# CANTensegrityBoard.net
KiCad netlist of a schematic drawn in EAGLE
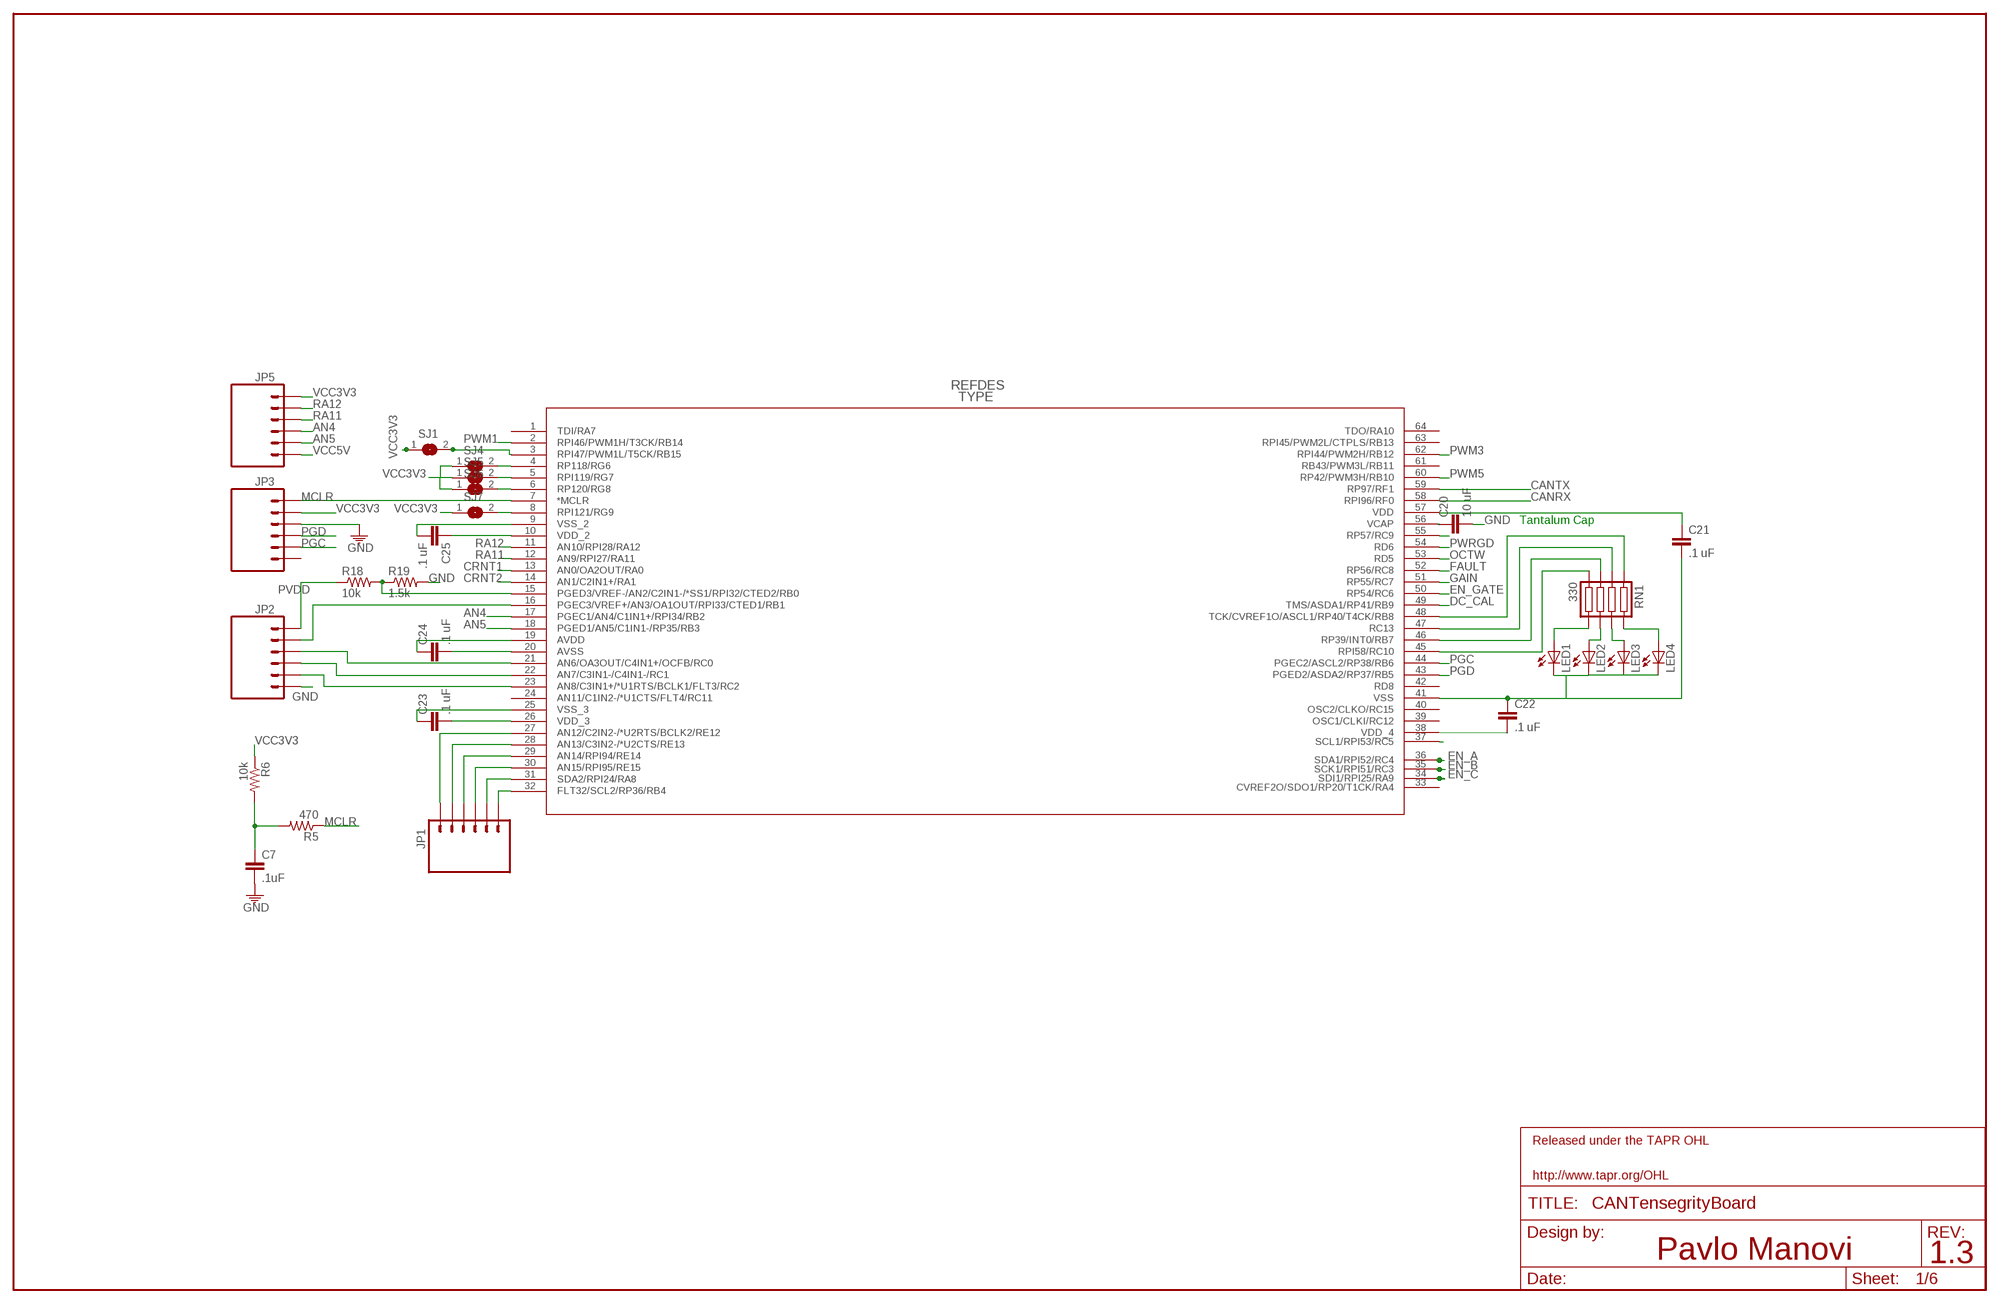
[diagram p0: schematic, sheet 1]
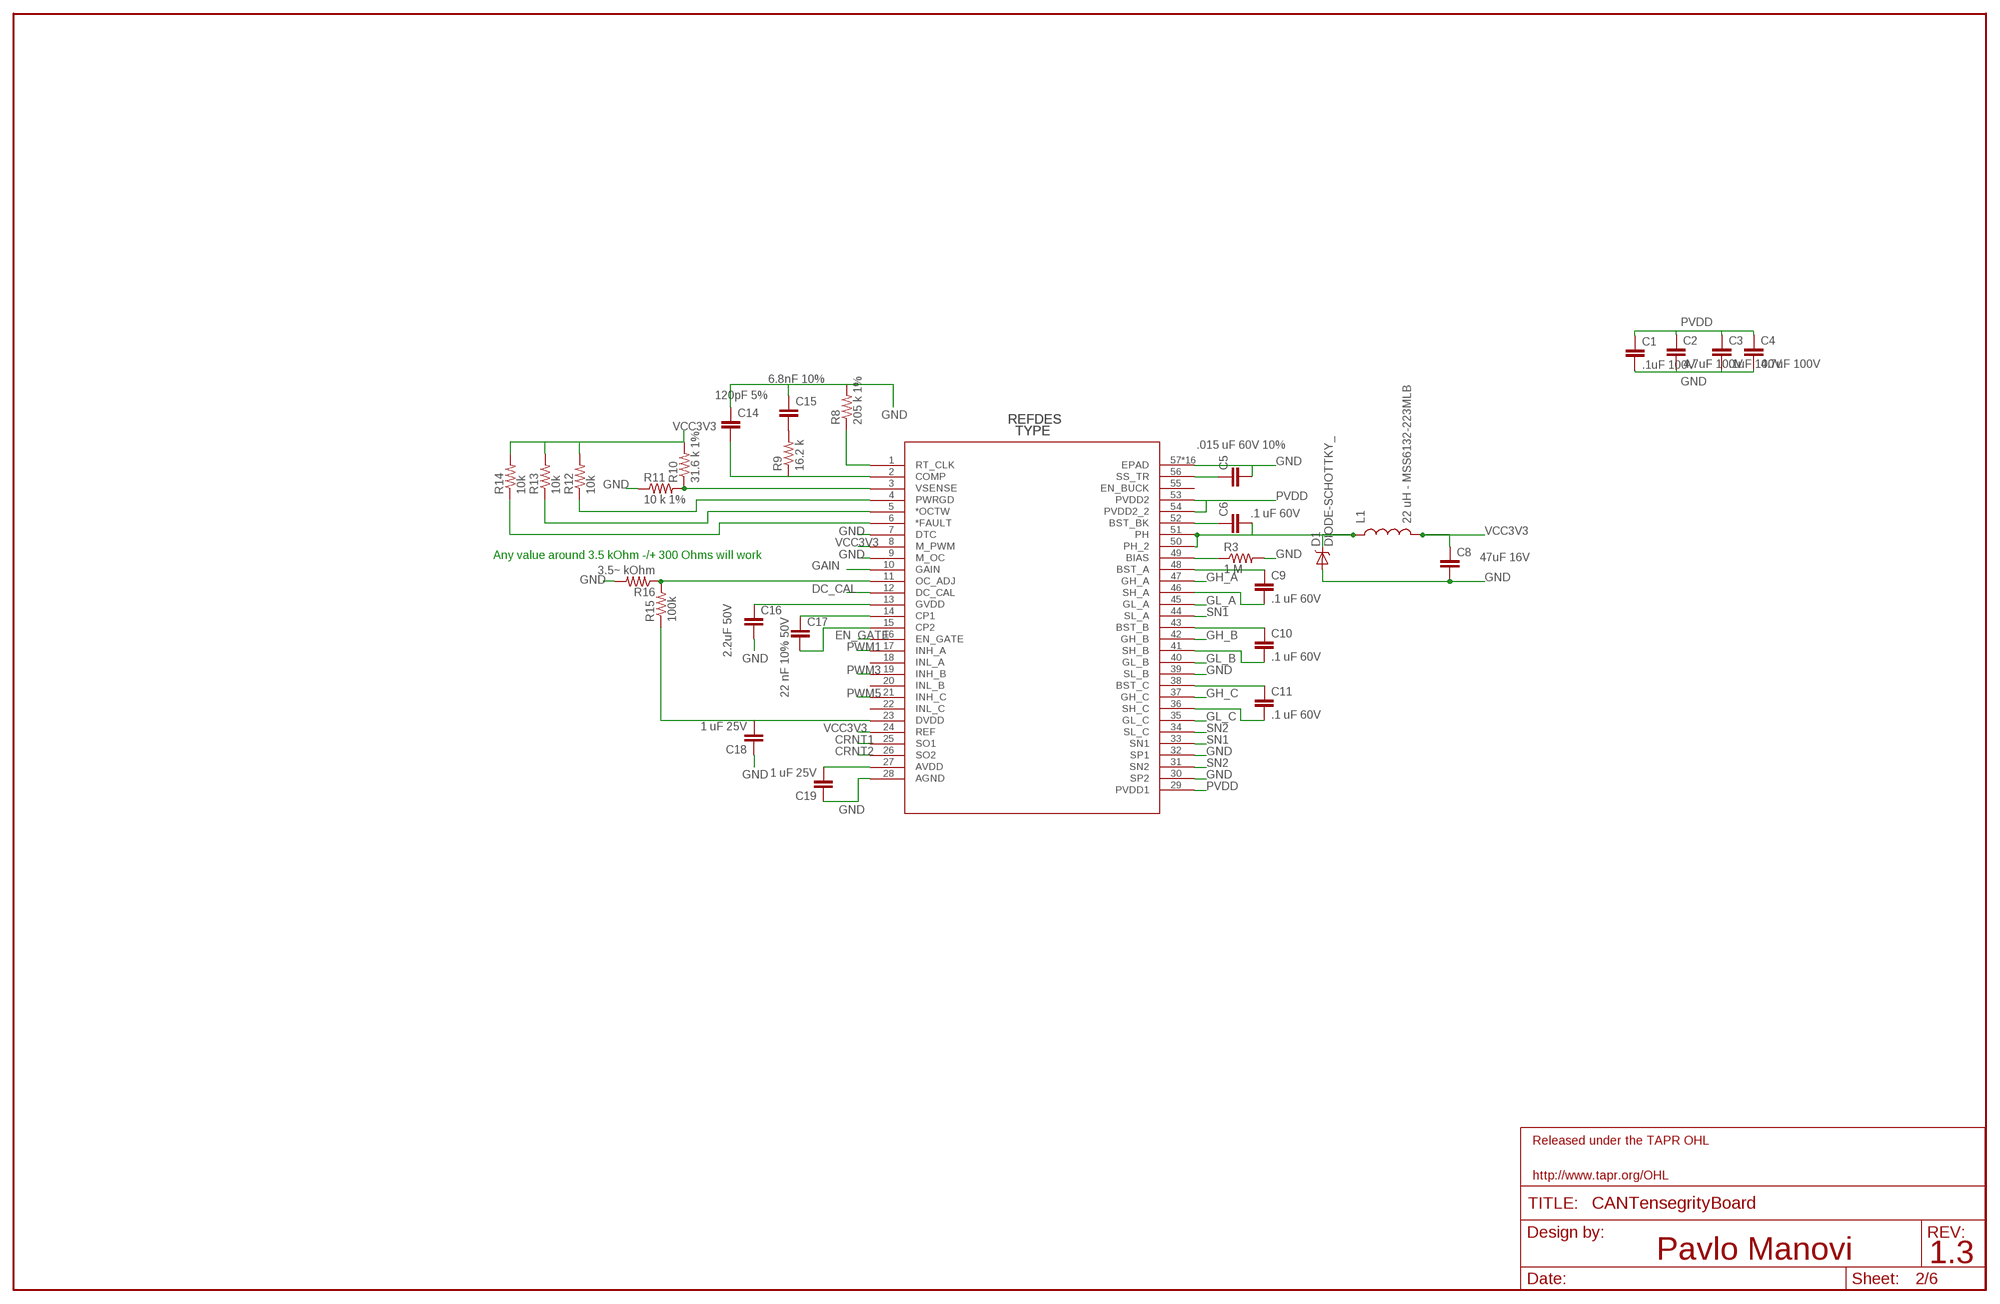
[diagram p1: schematic, sheet 2]
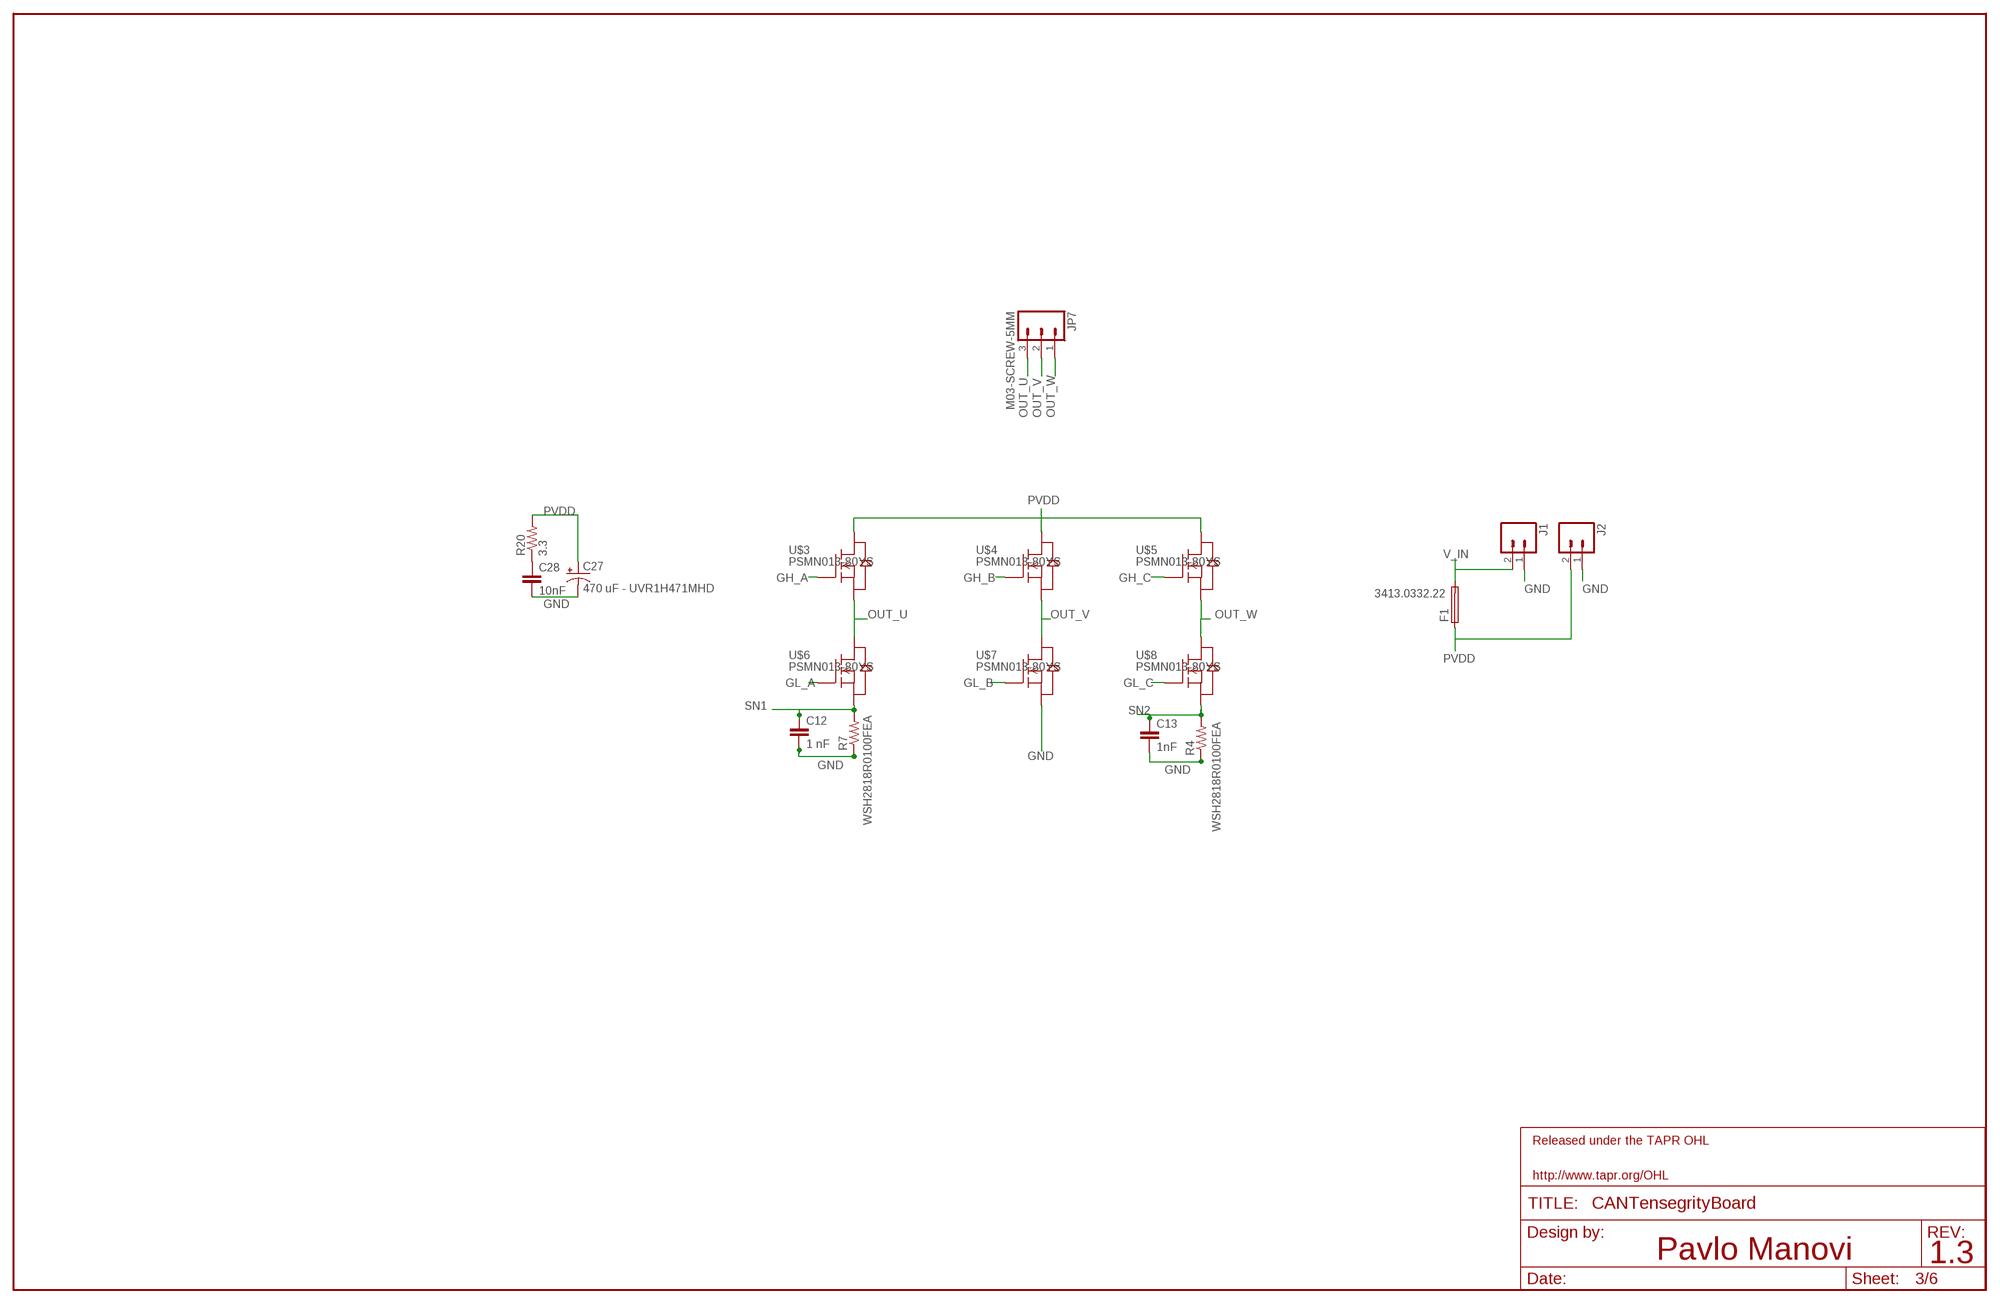
[diagram p2: schematic, sheet 3]
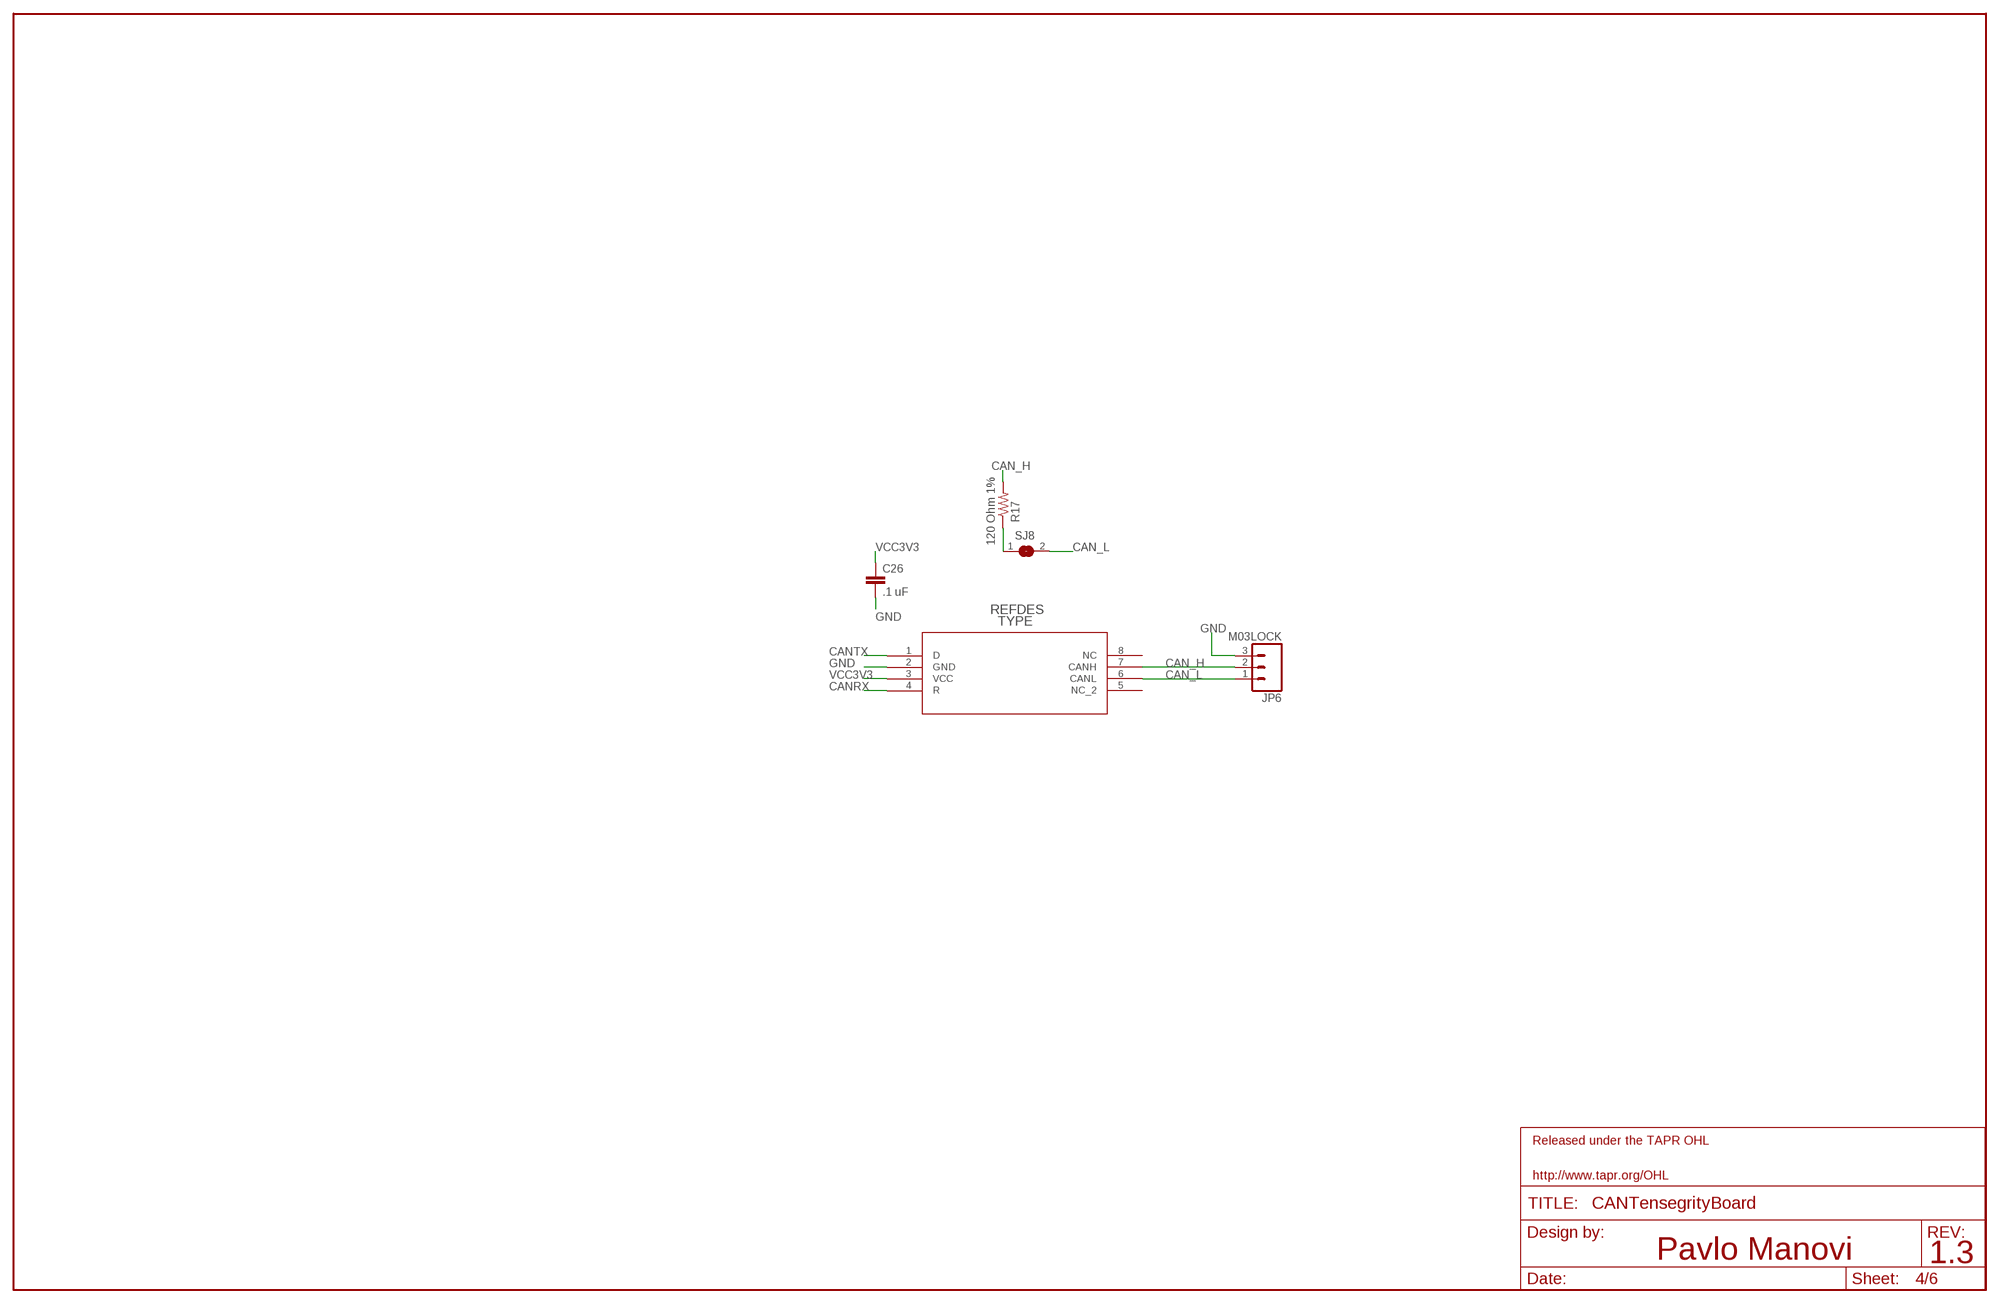
[diagram p3: schematic, sheet 4]
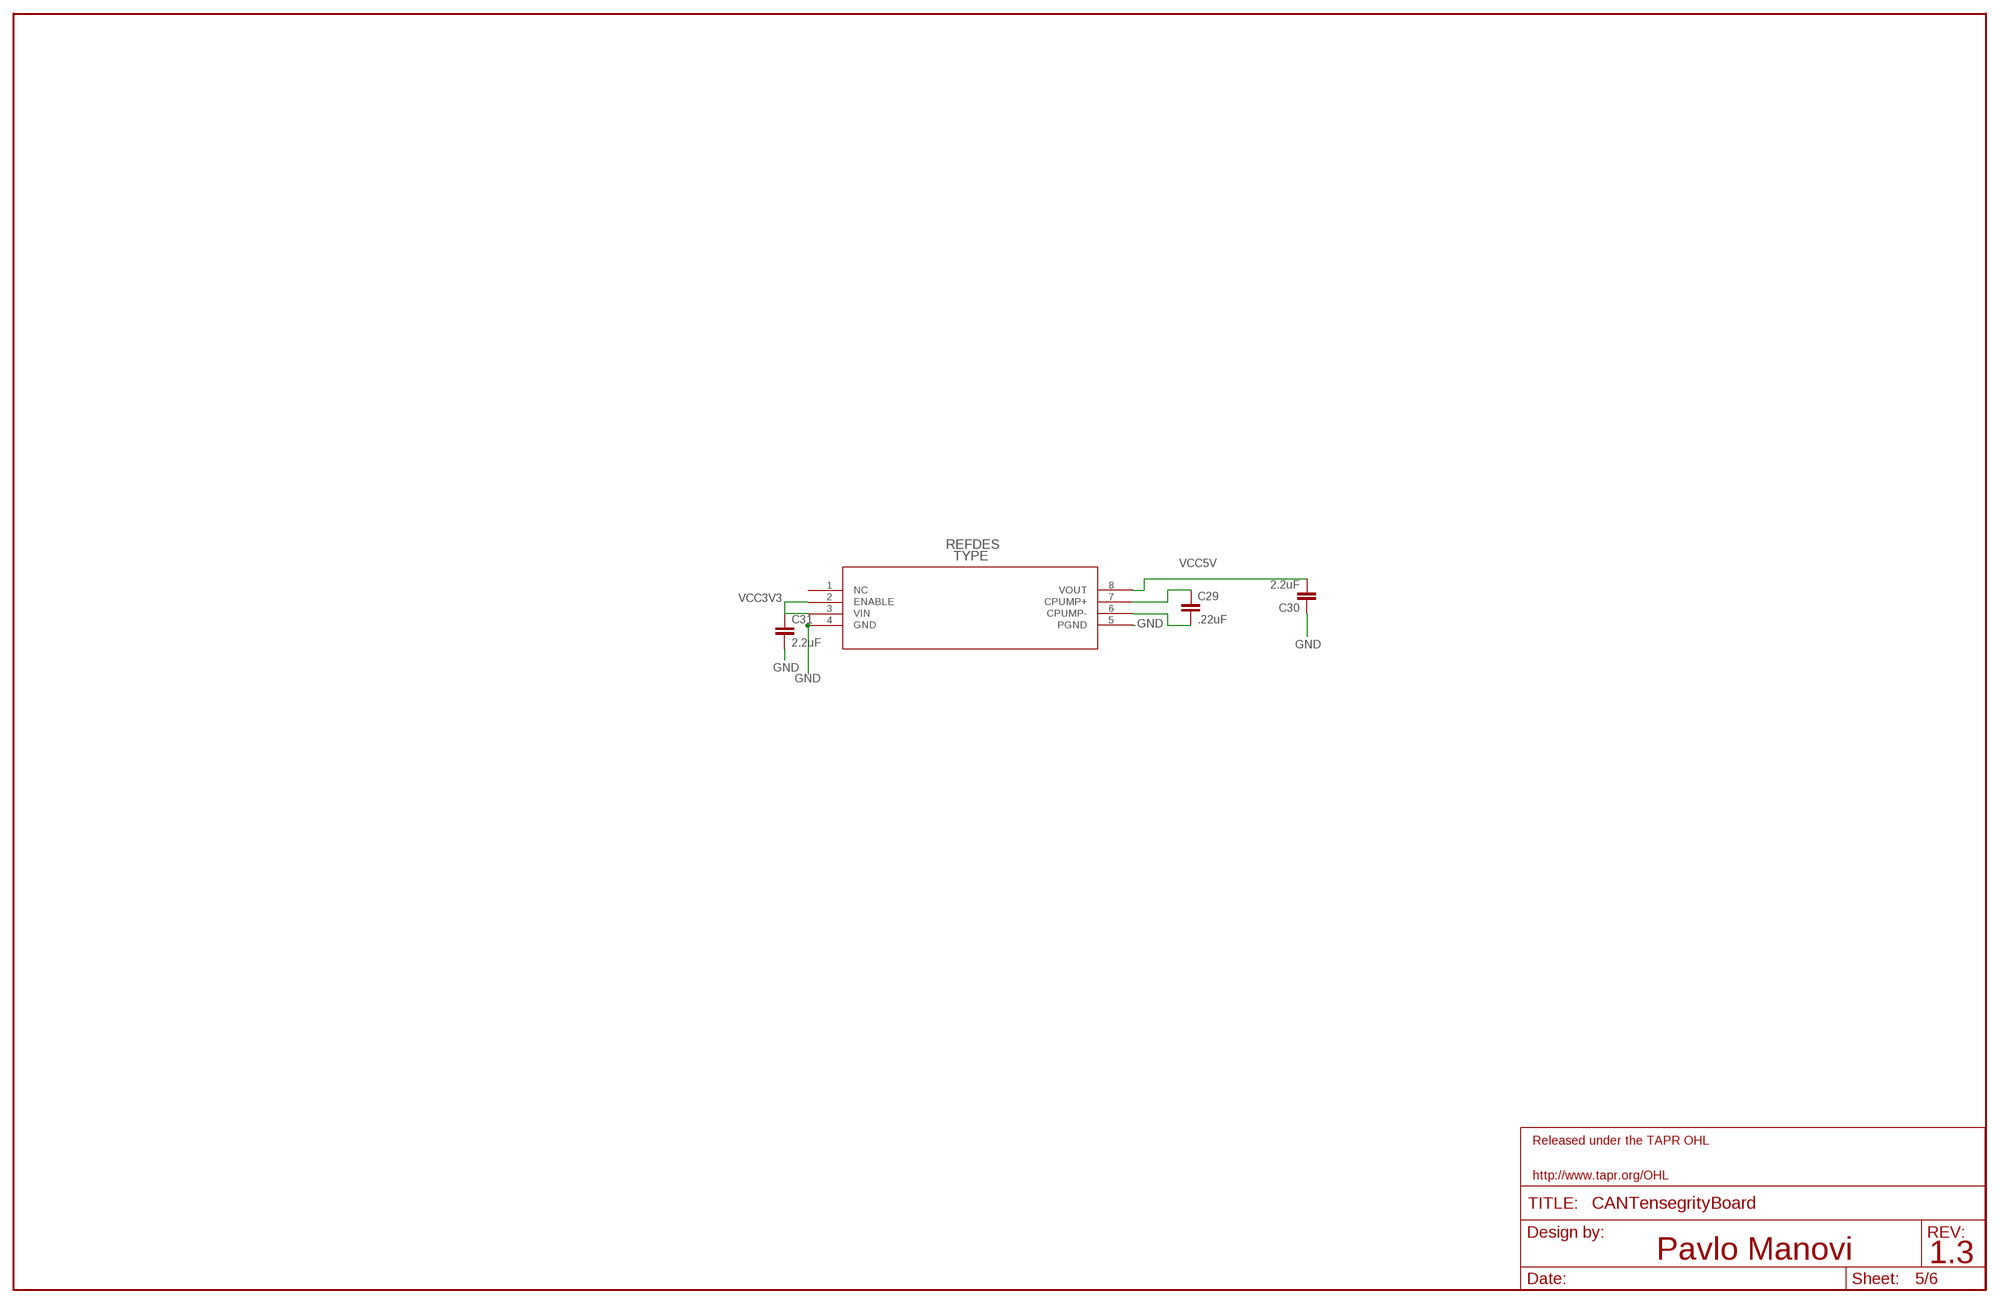
[diagram p4: schematic, sheet 5]
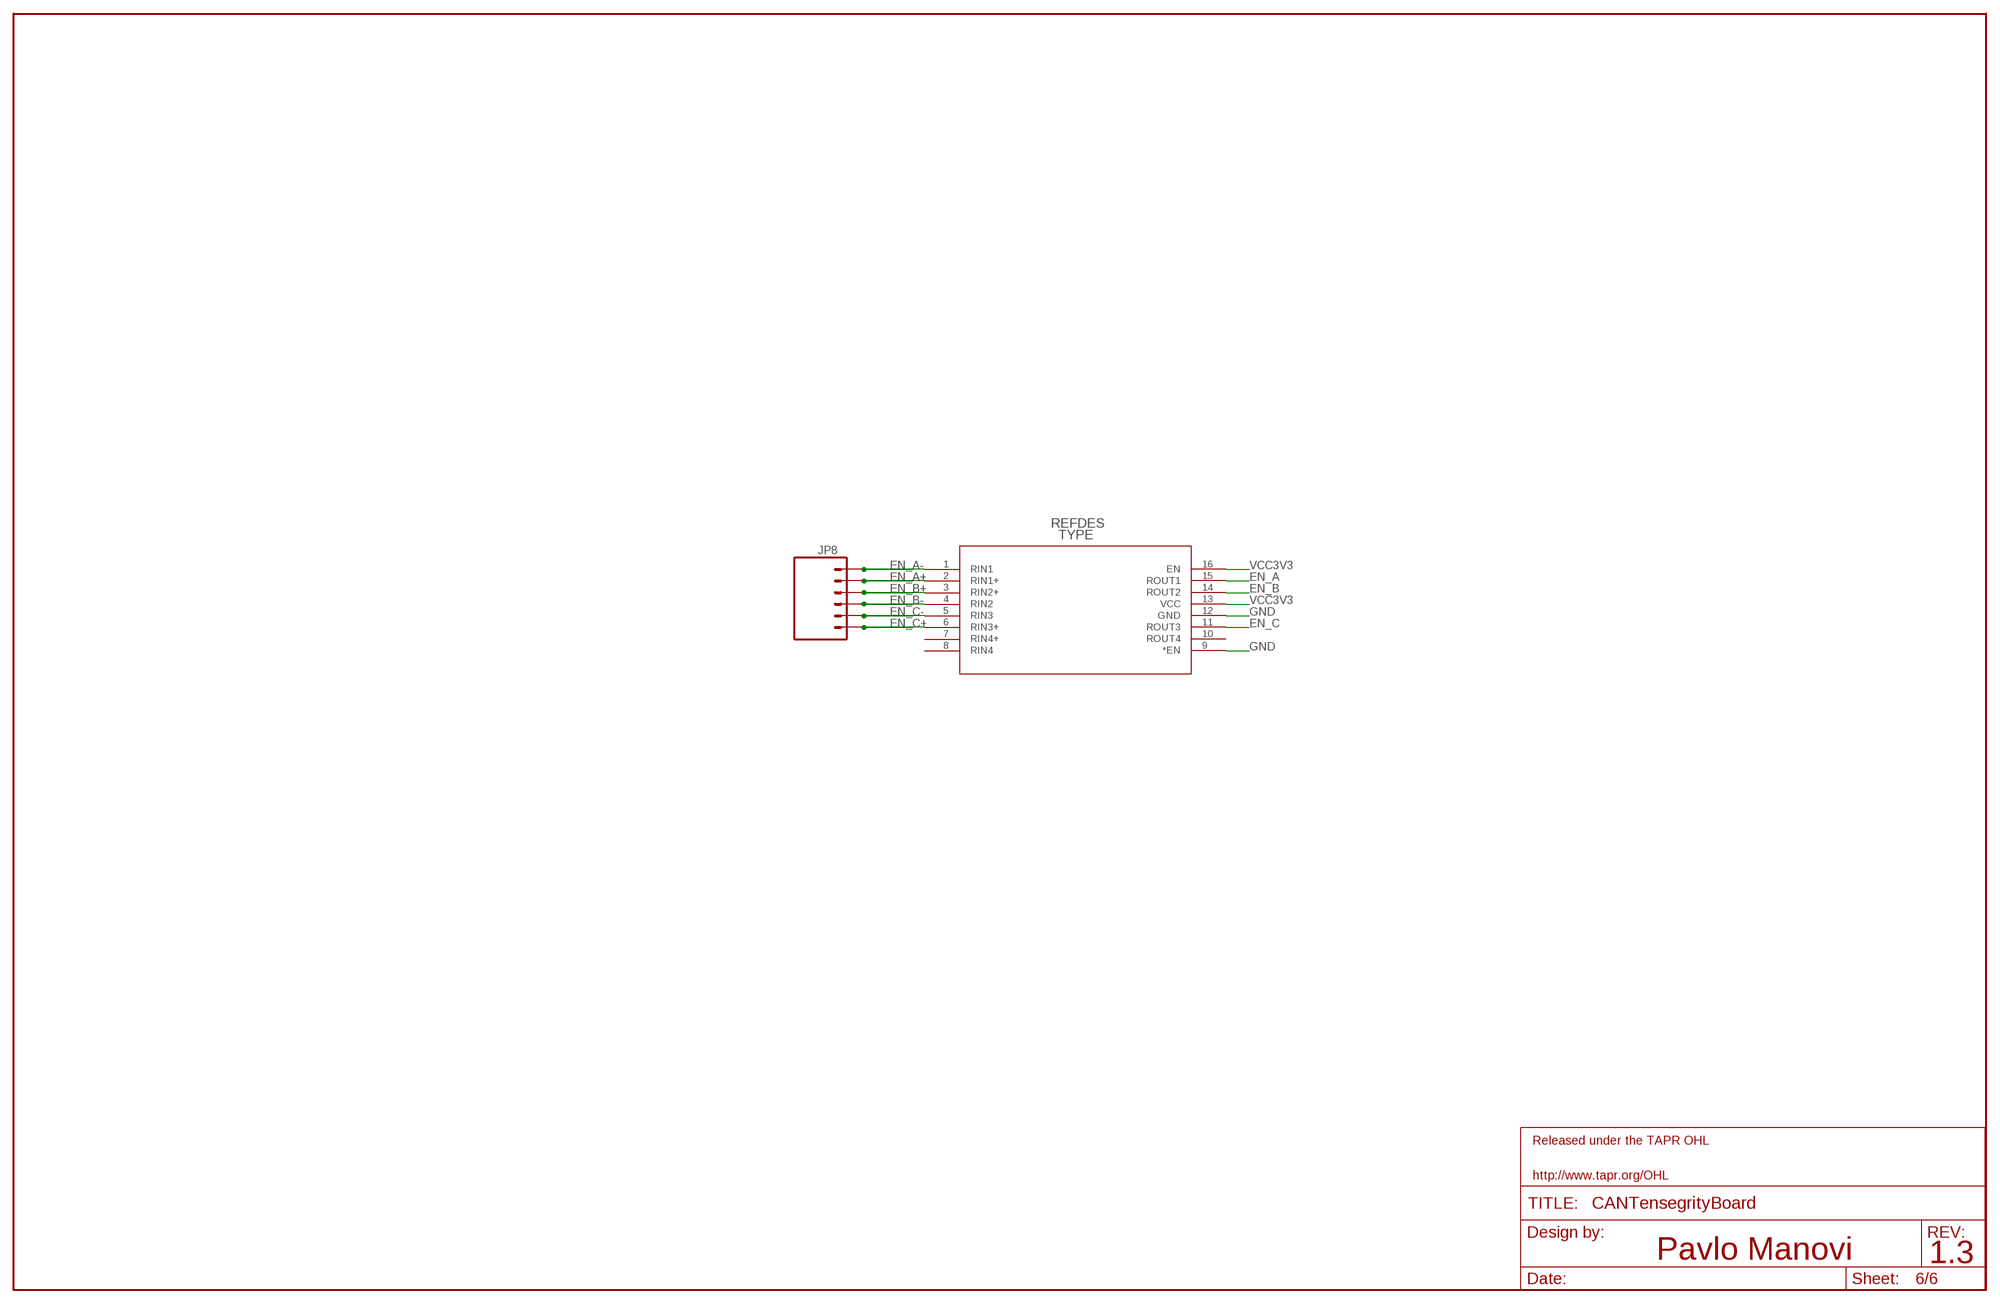
[diagram p5: schematic, sheet 6]

(export (version "E")
  (design (tool "Eeschema 10.0.6"))
  (components
    (comp (ref "C7")
      (value ".1uF")
      (footprint "eagle-import:0805")
      (libsource (lib "eagle-import") (part "CAP0805"))
    )
    (comp (ref "C20")
      (value "10 uF")
      (footprint "eagle-import:1206")
      (libsource (lib "eagle-import") (part "CAP1206"))
    )
    (comp (ref "C21")
      (value ".1 uF")
      (footprint "eagle-import:0805")
      (libsource (lib "eagle-import") (part "CAP0805"))
    )
    (comp (ref "C22")
      (value ".1 uF")
      (footprint "eagle-import:0805")
      (libsource (lib "eagle-import") (part "CAP0805"))
    )
    (comp (ref "C23")
      (value ".1 uF")
      (footprint "eagle-import:0805")
      (libsource (lib "eagle-import") (part "CAP0805"))
    )
    (comp (ref "C24")
      (value ".1 uF")
      (footprint "eagle-import:0805")
      (libsource (lib "eagle-import") (part "CAP0805"))
    )
    (comp (ref "C25")
      (value ".1 uF")
      (footprint "eagle-import:0805")
      (libsource (lib "eagle-import") (part "CAP0805"))
    )
    (comp (ref "JP1")
      (value "M06SIP")
      (footprint "eagle-import:1X06")
      (libsource (lib "eagle-import") (part "M06SIP"))
    )
    (comp (ref "JP2")
      (value "M06SIP")
      (footprint "eagle-import:1X06")
      (libsource (lib "eagle-import") (part "M06SIP"))
    )
    (comp (ref "JP3")
      (value "M06LOCK")
      (footprint "eagle-import:1X06_LOCK")
      (libsource (lib "eagle-import") (part "CMPE118lib_M06LOCK"))
    )
    (comp (ref "JP5")
      (value "M06LOCK")
      (footprint "eagle-import:1X06_LOCK")
      (libsource (lib "eagle-import") (part "CMPE118lib_M06LOCK"))
    )
    (comp (ref "LED1")
      (value "LED0805")
      (footprint "eagle-import:LED-0805")
      (libsource (lib "eagle-import") (part "LED0805"))
    )
    (comp (ref "LED2")
      (value "LED0805")
      (footprint "eagle-import:LED-0805")
      (libsource (lib "eagle-import") (part "LED0805"))
    )
    (comp (ref "LED3")
      (value "LED0805")
      (footprint "eagle-import:LED-0805")
      (libsource (lib "eagle-import") (part "LED0805"))
    )
    (comp (ref "LED4")
      (value "LED0805")
      (footprint "eagle-import:LED-0805")
      (libsource (lib "eagle-import") (part "LED0805"))
    )
    (comp (ref "R5")
      (value "470")
      (footprint "eagle-import:0805")
      (libsource (lib "eagle-import") (part "CMPE118lib_RESISTOR0805-RES"))
    )
    (comp (ref "R6")
      (value "10k")
      (footprint "eagle-import:0805")
      (libsource (lib "eagle-import") (part "CMPE118lib_RESISTOR0805-RES"))
    )
    (comp (ref "R18")
      (value "10k")
      (footprint "eagle-import:0805")
      (libsource (lib "eagle-import") (part "RESISTOR0805-RES"))
    )
    (comp (ref "R19")
      (value "1.5k")
      (footprint "eagle-import:0805")
      (libsource (lib "eagle-import") (part "RESISTOR0805-RES"))
    )
    (comp (ref "RN1")
      (value "330")
      (footprint "eagle-import:EXB-38V271JV")
      (libsource (lib "eagle-import") (part "RESISTOR_ARRAY-4"))
    )
    (comp (ref "SJ1") (value "SJ") (footprint "eagle-import:SJ") (libsource (lib "eagle-import") (part "SJ")))
    (comp (ref "SJ4") (value "SJ") (footprint "eagle-import:SJ") (libsource (lib "eagle-import") (part "SJ")))
    (comp (ref "SJ5") (value "SJ") (footprint "eagle-import:SJ") (libsource (lib "eagle-import") (part "SJ")))
    (comp (ref "SJ6") (value "SJ") (footprint "eagle-import:SJ") (libsource (lib "eagle-import") (part "SJ")))
    (comp (ref "SJ7") (value "SJ") (footprint "eagle-import:SJ") (libsource (lib "eagle-import") (part "SJ")))
    (comp (ref "U$1")
      (value "DSPIC33EP128MC502-I/SS")
      (footprint "eagle-import:QFP64-10X10MC")
      (libsource (lib "eagle-import") (part "DSPIC33EP256MC50"))
    )
    (comp (ref "C29")
      (value ".22uF")
      (footprint "eagle-import:0805")
      (libsource (lib "eagle-import") (part "CAP0805"))
    )
    (comp (ref "C30")
      (value "2.2uF")
      (footprint "eagle-import:0805")
      (libsource (lib "eagle-import") (part "CAP0805"))
    )
    (comp (ref "C31")
      (value "2.2uF")
      (footprint "eagle-import:0805")
      (libsource (lib "eagle-import") (part "CAP0805"))
    )
    (comp (ref "U1")
      (value "REG711-5_DGK_8")
      (footprint "eagle-import:DGK8")
      (libsource (lib "eagle-import") (part "REG711-5_DGK_8"))
    )
    (comp (ref "JP8")
      (value "M06SIP_LOCK")
      (footprint "eagle-import:1X06-SIP_LOCK")
      (libsource (lib "eagle-import") (part "M06SIP_LOCK"))
    )
    (comp (ref "U3")
      (value "SN65LVDT348_PW_1")
      (footprint "eagle-import:PW16")
      (libsource (lib "eagle-import") (part "SN65LVDT348_PW_1"))
    )
    (comp (ref "C12")
      (value "1 nF")
      (footprint "eagle-import:0805")
      (libsource (lib "eagle-import") (part "CAP0805"))
    )
    (comp (ref "C13")
      (value "1nF")
      (footprint "eagle-import:0805")
      (libsource (lib "eagle-import") (part "CAP0805"))
    )
    (comp (ref "C27")
      (value "470 uF - UVR1H471MHD")
      (footprint "eagle-import:CPOL-RADIAL-1000UF-25V")
      (libsource (lib "eagle-import") (part "CAP_POLPTH4"))
    )
    (comp (ref "C28")
      (value "10nF")
      (footprint "eagle-import:0805")
      (libsource (lib "eagle-import") (part "CAP0805"))
    )
    (comp (ref "F1")
      (value "3413.0332.22")
      (footprint "eagle-import:LED-1206")
      (libsource (lib "eagle-import") (part "TE5"))
    )
    (comp (ref "J1")
      (value "M02PTH4")
      (footprint "eagle-import:1X02_XTRA_BIG")
      (libsource (lib "eagle-import") (part "M02PTH4"))
    )
    (comp (ref "J2")
      (value "M02PTH4")
      (footprint "eagle-import:1X02_XTRA_BIG")
      (libsource (lib "eagle-import") (part "M02PTH4"))
    )
    (comp (ref "JP7")
      (value "M03-SCREW-5MM")
      (footprint "eagle-import:SCREWTERMINAL-5MM-3")
      (libsource (lib "eagle-import") (part "pavlo_M03-SCREW-5MM"))
    )
    (comp (ref "R4")
      (value "WSH2818R0100FEA")
      (footprint "eagle-import:SMT-REF")
      (libsource (lib "eagle-import") (part "RESISTOR"))
    )
    (comp (ref "R7")
      (value "WSH2818R0100FEA")
      (footprint "eagle-import:SMT-REF")
      (libsource (lib "eagle-import") (part "RESISTOR"))
    )
    (comp (ref "R20")
      (value "3.3")
      (footprint "eagle-import:0805")
      (libsource (lib "eagle-import") (part "RESISTOR0805-RES"))
    )
    (comp (ref "U$3")
      (value "PSMN013-80YS")
      (footprint "eagle-import:TO127P600X120-5N")
      (libsource (lib "eagle-import") (part "PSMN013-80YS"))
    )
    (comp (ref "U$4")
      (value "PSMN013-80YS")
      (footprint "eagle-import:TO127P600X120-5N")
      (libsource (lib "eagle-import") (part "PSMN013-80YS"))
    )
    (comp (ref "U$5")
      (value "PSMN013-80YS")
      (footprint "eagle-import:TO127P600X120-5N")
      (libsource (lib "eagle-import") (part "PSMN013-80YS"))
    )
    (comp (ref "U$6")
      (value "PSMN013-80YS")
      (footprint "eagle-import:TO127P600X120-5N")
      (libsource (lib "eagle-import") (part "PSMN013-80YS"))
    )
    (comp (ref "U$7")
      (value "PSMN013-80YS")
      (footprint "eagle-import:TO127P600X120-5N")
      (libsource (lib "eagle-import") (part "PSMN013-80YS"))
    )
    (comp (ref "U$8")
      (value "PSMN013-80YS")
      (footprint "eagle-import:TO127P600X120-5N")
      (libsource (lib "eagle-import") (part "PSMN013-80YS"))
    )
    (comp (ref "C1")
      (value ".1uF 100V")
      (footprint "eagle-import:0805")
      (libsource (lib "eagle-import") (part "CAP0805"))
    )
    (comp (ref "C2")
      (value "4.7uF 100V")
      (footprint "eagle-import:1206")
      (libsource (lib "eagle-import") (part "CAP1206"))
    )
    (comp (ref "C3")
      (value ".1uF 100V")
      (footprint "eagle-import:0805")
      (libsource (lib "eagle-import") (part "CAP0805"))
    )
    (comp (ref "C4")
      (value "4.7uF 100V")
      (footprint "eagle-import:1206")
      (libsource (lib "eagle-import") (part "CAP1206"))
    )
    (comp (ref "C5")
      (value ".015 uF 60V 10%")
      (footprint "eagle-import:0805")
      (libsource (lib "eagle-import") (part "CAP0805"))
    )
    (comp (ref "C6")
      (value ".1 uF 60V")
      (footprint "eagle-import:0805")
      (libsource (lib "eagle-import") (part "CAP0805"))
    )
    (comp (ref "C8")
      (value "47uF 16V")
      (footprint "eagle-import:1206")
      (libsource (lib "eagle-import") (part "CAP1206"))
    )
    (comp (ref "C9")
      (value ".1 uF 60V")
      (footprint "eagle-import:0805")
      (libsource (lib "eagle-import") (part "CAP0805"))
    )
    (comp (ref "C10")
      (value ".1 uF 60V")
      (footprint "eagle-import:0805")
      (libsource (lib "eagle-import") (part "CAP0805"))
    )
    (comp (ref "C11")
      (value ".1 uF 60V")
      (footprint "eagle-import:0805")
      (libsource (lib "eagle-import") (part "CAP0805"))
    )
    (comp (ref "C14")
      (value "120pF 5%")
      (footprint "eagle-import:0805")
      (libsource (lib "eagle-import") (part "CAP0805"))
    )
    (comp (ref "C15")
      (value "6.8nF 10%")
      (footprint "eagle-import:0805")
      (libsource (lib "eagle-import") (part "CAP0805"))
    )
    (comp (ref "C16")
      (value "2.2uF 50V")
      (footprint "eagle-import:1206")
      (libsource (lib "eagle-import") (part "CAP1206"))
    )
    (comp (ref "C17")
      (value "22 nF 10% 50V")
      (footprint "eagle-import:0805")
      (libsource (lib "eagle-import") (part "CAP0805"))
    )
    (comp (ref "C18")
      (value "1 uF 25V")
      (footprint "eagle-import:0805")
      (libsource (lib "eagle-import") (part "CAP0805"))
    )
    (comp (ref "C19")
      (value "1 uF 25V")
      (footprint "eagle-import:0805")
      (libsource (lib "eagle-import") (part "CAP0805"))
    )
    (comp (ref "D1")
      (value "DIODE-SCHOTTKY_")
      (footprint "eagle-import:SMA-DIODE")
      (libsource (lib "eagle-import") (part "DIODE-SCHOTTKY_"))
    )
    (comp (ref "L1")
      (value "22 uH - MSS6132-223MLB")
      (footprint "eagle-import:MSS6132")
      (libsource (lib "eagle-import") (part "INDUCTOR"))
    )
    (comp (ref "R3")
      (value "1 M")
      (footprint "eagle-import:0805")
      (libsource (lib "eagle-import") (part "RESISTOR0805-RES"))
    )
    (comp (ref "R8")
      (value "205 k 1%")
      (footprint "eagle-import:0805")
      (libsource (lib "eagle-import") (part "RESISTOR0805-RES"))
    )
    (comp (ref "R9")
      (value "16.2 k")
      (footprint "eagle-import:0805")
      (libsource (lib "eagle-import") (part "RESISTOR0805-RES"))
    )
    (comp (ref "R10")
      (value "31.6 k 1%")
      (footprint "eagle-import:0805")
      (libsource (lib "eagle-import") (part "RESISTOR0805-RES"))
    )
    (comp (ref "R11")
      (value "10 k 1%")
      (footprint "eagle-import:0805")
      (libsource (lib "eagle-import") (part "RESISTOR0805-RES"))
    )
    (comp (ref "R12")
      (value "10k")
      (footprint "eagle-import:0805")
      (libsource (lib "eagle-import") (part "RESISTOR0805-RES"))
    )
    (comp (ref "R13")
      (value "10k")
      (footprint "eagle-import:0805")
      (libsource (lib "eagle-import") (part "RESISTOR0805-RES"))
    )
    (comp (ref "R14")
      (value "10k")
      (footprint "eagle-import:0805")
      (libsource (lib "eagle-import") (part "RESISTOR0805-RES"))
    )
    (comp (ref "R15")
      (value "100k")
      (footprint "eagle-import:0805")
      (libsource (lib "eagle-import") (part "RESISTOR0805-RES"))
    )
    (comp (ref "R16")
      (value "3.5~ kOhm")
      (footprint "eagle-import:0805")
      (libsource (lib "eagle-import") (part "RESISTOR0805-RES"))
    )
    (comp (ref "U$2")
      (value "DRV8302")
      (footprint "eagle-import:DCA56_6P35X3P600")
      (libsource (lib "eagle-import") (part "DRV8302"))
    )
    (comp (ref "C26")
      (value ".1 uF")
      (footprint "eagle-import:0805")
      (libsource (lib "eagle-import") (part "CAP0805"))
    )
    (comp (ref "JP6")
      (value "M03LOCK")
      (footprint "eagle-import:1X03_LOCK")
      (libsource (lib "eagle-import") (part "M03LOCK"))
    )
    (comp (ref "R17")
      (value "120 Ohm 1%")
      (footprint "eagle-import:0805")
      (libsource (lib "eagle-import") (part "RESISTOR0805-RES"))
    )
    (comp (ref "SJ8") (value "SJ") (footprint "eagle-import:SJ") (libsource (lib "eagle-import") (part "SJ")))
    (comp (ref "U2")
      (value "SN65HVD232_D_8")
      (footprint "eagle-import:D8")
      (libsource (lib "eagle-import") (part "SN65HVD232_D_8"))
    )
  )
  (nets
    (net (code "1") (name "AN4") (class "Default")
      (node (ref "JP5") (pin "4") (pinfunction "4_4") (pintype "passive"))
      (node (ref "U$1") (pin "17") (pinfunction "PGEC1/AN4/C1IN1+/RPI34/RB2_17") (pintype "passive"))
    )
    (net (code "2") (name "AN5") (class "Default")
      (node (ref "JP5") (pin "5") (pinfunction "5_5") (pintype "passive"))
      (node (ref "U$1") (pin "18") (pinfunction "PGED1/AN5/C1IN1-/RP35/RB3_18") (pintype "passive"))
    )
    (net (code "3") (name "CANRX") (class "Default")
      (node (ref "U$1") (pin "58") (pinfunction "RPI96/RF0_58") (pintype "passive"))
      (node (ref "U2") (pin "4") (pinfunction "R_4") (pintype "passive"))
    )
    (net (code "4") (name "CANTX") (class "Default")
      (node (ref "U$1") (pin "59") (pinfunction "RP97/RF1_59") (pintype "passive"))
      (node (ref "U2") (pin "1") (pinfunction "D_1") (pintype "passive"))
    )
    (net (code "5") (name "CAN_H") (class "Default")
      (node (ref "JP6") (pin "2") (pinfunction "2_2") (pintype "passive"))
      (node (ref "R17") (pin "2") (pinfunction "2_2") (pintype "passive"))
      (node (ref "U2") (pin "7") (pinfunction "CANH_7") (pintype "passive"))
    )
    (net (code "6") (name "CAN_L") (class "Default")
      (node (ref "JP6") (pin "1") (pinfunction "1_1") (pintype "passive"))
      (node (ref "SJ8") (pin "2") (pinfunction "2_2") (pintype "passive"))
      (node (ref "U2") (pin "6") (pinfunction "CANL_6") (pintype "passive"))
    )
    (net (code "7") (name "CRNT1") (class "Default")
      (node (ref "U$1") (pin "13") (pinfunction "AN0/OA2OUT/RA0_13") (pintype "passive"))
      (node (ref "U$2") (pin "25") (pinfunction "SO1_25") (pintype "passive"))
    )
    (net (code "8") (name "CRNT2") (class "Default")
      (node (ref "U$1") (pin "14") (pinfunction "AN1/C2IN1+/RA1_14") (pintype "passive"))
      (node (ref "U$2") (pin "26") (pinfunction "SO2_26") (pintype "passive"))
    )
    (net (code "9") (name "DC_CAL") (class "Default")
      (node (ref "U$1") (pin "49") (pinfunction "TMS/ASDA1/RP41/RB9_49") (pintype "passive"))
      (node (ref "U$2") (pin "12") (pinfunction "DC_CAL_12") (pintype "passive"))
    )
    (net (code "10") (name "EN_A") (class "Default")
      (node (ref "U$1") (pin "36") (pinfunction "SDA1/RPI52/RC4_36") (pintype "passive"))
      (node (ref "U3") (pin "15") (pinfunction "ROUT1_15") (pintype "passive"))
    )
    (net (code "11") (name "EN_A+") (class "Default")
      (node (ref "JP8") (pin "2") (pinfunction "2_2") (pintype "passive"))
      (node (ref "U3") (pin "2") (pinfunction "RIN1+_2") (pintype "passive"))
    )
    (net (code "12") (name "EN_A-") (class "Default")
      (node (ref "JP8") (pin "1") (pinfunction "1_1") (pintype "passive"))
      (node (ref "U3") (pin "1") (pinfunction "RIN1_1") (pintype "passive"))
    )
    (net (code "13") (name "EN_B") (class "Default")
      (node (ref "U$1") (pin "35") (pinfunction "SCK1/RPI51/RC3_35") (pintype "passive"))
      (node (ref "U3") (pin "14") (pinfunction "ROUT2_14") (pintype "passive"))
    )
    (net (code "14") (name "EN_B+") (class "Default")
      (node (ref "JP8") (pin "3") (pinfunction "3_3") (pintype "passive"))
      (node (ref "U3") (pin "3") (pinfunction "RIN2+_3") (pintype "passive"))
    )
    (net (code "15") (name "EN_B-") (class "Default")
      (node (ref "JP8") (pin "4") (pinfunction "4_4") (pintype "passive"))
      (node (ref "U3") (pin "4") (pinfunction "RIN2_4") (pintype "passive"))
    )
    (net (code "16") (name "EN_C") (class "Default")
      (node (ref "U$1") (pin "34") (pinfunction "SDI1/RPI25/RA9_34") (pintype "passive"))
      (node (ref "U3") (pin "11") (pinfunction "ROUT3_11") (pintype "passive"))
    )
    (net (code "17") (name "EN_C+") (class "Default")
      (node (ref "JP8") (pin "6") (pinfunction "6_6") (pintype "passive"))
      (node (ref "U3") (pin "6") (pinfunction "RIN3+_6") (pintype "passive"))
    )
    (net (code "18") (name "EN_C-") (class "Default")
      (node (ref "JP8") (pin "5") (pinfunction "5_5") (pintype "passive"))
      (node (ref "U3") (pin "5") (pinfunction "RIN3_5") (pintype "passive"))
    )
    (net (code "19") (name "EN_GATE") (class "Default")
      (node (ref "U$1") (pin "50") (pinfunction "RP54/RC6_50") (pintype "passive"))
      (node (ref "U$2") (pin "16") (pinfunction "EN_GATE_16") (pintype "passive"))
    )
    (net (code "20") (name "FAULT") (class "Default")
      (node (ref "R14") (pin "1") (pinfunction "1_1") (pintype "passive"))
      (node (ref "U$1") (pin "52") (pinfunction "RP56/RC8_52") (pintype "passive"))
      (node (ref "U$2") (pin "6") (pinfunction "*FAULT_6") (pintype "passive"))
    )
    (net (code "21") (name "GAIN") (class "Default")
      (node (ref "U$1") (pin "51") (pinfunction "RP55/RC7_51") (pintype "passive"))
      (node (ref "U$2") (pin "10") (pinfunction "GAIN_10") (pintype "passive"))
    )
    (net (code "22") (name "GH_A") (class "Default")
      (node (ref "U$2") (pin "47") (pinfunction "GH_A_47") (pintype "passive"))
      (node (ref "U$3") (pin "4") (pinfunction "G_4") (pintype "passive"))
    )
    (net (code "23") (name "GH_B") (class "Default")
      (node (ref "U$2") (pin "42") (pinfunction "GH_B_42") (pintype "passive"))
      (node (ref "U$4") (pin "4") (pinfunction "G_4") (pintype "passive"))
    )
    (net (code "24") (name "GH_C") (class "Default")
      (node (ref "U$2") (pin "37") (pinfunction "GH_C_37") (pintype "passive"))
      (node (ref "U$5") (pin "4") (pinfunction "G_4") (pintype "passive"))
    )
    (net (code "25") (name "GL_A") (class "Default")
      (node (ref "U$2") (pin "45") (pinfunction "GL_A_45") (pintype "passive"))
      (node (ref "U$6") (pin "4") (pinfunction "G_4") (pintype "passive"))
    )
    (net (code "26") (name "GL_B") (class "Default")
      (node (ref "U$2") (pin "40") (pinfunction "GL_B_40") (pintype "passive"))
      (node (ref "U$7") (pin "4") (pinfunction "G_4") (pintype "passive"))
    )
    (net (code "27") (name "GL_C") (class "Default")
      (node (ref "U$2") (pin "35") (pinfunction "GL_C_35") (pintype "passive"))
      (node (ref "U$8") (pin "4") (pinfunction "G_4") (pintype "passive"))
    )
    (net (code "28") (name "GND") (class "Default")
      (node (ref "C1") (pin "2") (pinfunction "2_2") (pintype "passive"))
      (node (ref "C12") (pin "2") (pinfunction "2_2") (pintype "passive"))
      (node (ref "C13") (pin "2") (pinfunction "2_2") (pintype "passive"))
      (node (ref "C14") (pin "1") (pinfunction "1_1") (pintype "passive"))
      (node (ref "C15") (pin "1") (pinfunction "1_1") (pintype "passive"))
      (node (ref "C16") (pin "2") (pinfunction "2_2") (pintype "passive"))
      (node (ref "C18") (pin "1") (pinfunction "1_1") (pintype "passive"))
      (node (ref "C19") (pin "1") (pinfunction "1_1") (pintype "passive"))
      (node (ref "C2") (pin "2") (pinfunction "2_2") (pintype "passive"))
      (node (ref "C20") (pin "2") (pinfunction "2_2") (pintype "passive"))
      (node (ref "C21") (pin "2") (pinfunction "2_2") (pintype "passive"))
      (node (ref "C22") (pin "1") (pinfunction "1_1") (pintype "passive"))
      (node (ref "C26") (pin "2") (pinfunction "2_2") (pintype "passive"))
      (node (ref "C27") (pin "2") (pinfunction "-_2") (pintype "passive"))
      (node (ref "C28") (pin "2") (pinfunction "2_2") (pintype "passive"))
      (node (ref "C3") (pin "2") (pinfunction "2_2") (pintype "passive"))
      (node (ref "C30") (pin "1") (pinfunction "1_1") (pintype "passive"))
      (node (ref "C31") (pin "2") (pinfunction "2_2") (pintype "passive"))
      (node (ref "C4") (pin "2") (pinfunction "2_2") (pintype "passive"))
      (node (ref "C5") (pin "2") (pinfunction "2_2") (pintype "passive"))
      (node (ref "C7") (pin "2") (pinfunction "2_2") (pintype "passive"))
      (node (ref "C8") (pin "2") (pinfunction "2_2") (pintype "passive"))
      (node (ref "D1") (pin "A") (pinfunction "A_A") (pintype "passive"))
      (node (ref "J1") (pin "1") (pinfunction "2_1") (pintype "passive"))
      (node (ref "J2") (pin "1") (pinfunction "2_1") (pintype "passive"))
      (node (ref "JP2") (pin "6") (pinfunction "6_6") (pintype "passive"))
      (node (ref "JP3") (pin "3") (pinfunction "3_3") (pintype "passive"))
      (node (ref "JP6") (pin "3") (pinfunction "3_3") (pintype "passive"))
      (node (ref "LED1") (pin "2") (pinfunction "C_2") (pintype "passive"))
      (node (ref "LED2") (pin "2") (pinfunction "C_2") (pintype "passive"))
      (node (ref "LED3") (pin "2") (pinfunction "C_2") (pintype "passive"))
      (node (ref "LED4") (pin "2") (pinfunction "C_2") (pintype "passive"))
      (node (ref "R11") (pin "1") (pinfunction "1_1") (pintype "passive"))
      (node (ref "R16") (pin "2") (pinfunction "2_2") (pintype "passive"))
      (node (ref "R19") (pin "2") (pinfunction "2_2") (pintype "passive"))
      (node (ref "R3") (pin "2") (pinfunction "2_2") (pintype "passive"))
      (node (ref "R4") (pin "1") (pinfunction "1_1") (pintype "passive"))
      (node (ref "R7") (pin "1") (pinfunction "1_1") (pintype "passive"))
      (node (ref "R8") (pin "2") (pinfunction "2_2") (pintype "passive"))
      (node (ref "U$1") (pin "41") (pinfunction "VSS_41") (pintype "passive"))
      (node (ref "U$2") (pin "28") (pinfunction "AGND_28") (pintype "passive"))
      (node (ref "U$2") (pin "30") (pinfunction "SP2_30") (pintype "passive"))
      (node (ref "U$2") (pin "32") (pinfunction "SP1_32") (pintype "passive"))
      (node (ref "U$2") (pin "39") (pinfunction "SL_B_39") (pintype "passive"))
      (node (ref "U$2") (pin "57") (pinfunction "EPAD_57") (pintype "passive"))
      (node (ref "U$2") (pin "7") (pinfunction "DTC_7") (pintype "passive"))
      (node (ref "U$2") (pin "9") (pinfunction "M_OC_9") (pintype "passive"))
      (node (ref "U$2") (pin "P$1") (pinfunction "EPAD_P$1") (pintype "passive"))
      (node (ref "U$2") (pin "P$10") (pinfunction "EPAD_P$10") (pintype "passive"))
      (node (ref "U$2") (pin "P$11") (pinfunction "EPAD_P$11") (pintype "passive"))
      (node (ref "U$2") (pin "P$12") (pinfunction "EPAD_P$12") (pintype "passive"))
      (node (ref "U$2") (pin "P$13") (pinfunction "EPAD_P$13") (pintype "passive"))
      (node (ref "U$2") (pin "P$14") (pinfunction "EPAD_P$14") (pintype "passive"))
      (node (ref "U$2") (pin "P$15") (pinfunction "EPAD_P$15") (pintype "passive"))
      (node (ref "U$2") (pin "P$2") (pinfunction "EPAD_P$2") (pintype "passive"))
      (node (ref "U$2") (pin "P$3") (pinfunction "EPAD_P$3") (pintype "passive"))
      (node (ref "U$2") (pin "P$4") (pinfunction "EPAD_P$4") (pintype "passive"))
      (node (ref "U$2") (pin "P$5") (pinfunction "EPAD_P$5") (pintype "passive"))
      (node (ref "U$2") (pin "P$6") (pinfunction "EPAD_P$6") (pintype "passive"))
      (node (ref "U$2") (pin "P$7") (pinfunction "EPAD_P$7") (pintype "passive"))
      (node (ref "U$2") (pin "P$8") (pinfunction "EPAD_P$8") (pintype "passive"))
      (node (ref "U$2") (pin "P$9") (pinfunction "EPAD_P$9") (pintype "passive"))
      (node (ref "U$7") (pin "1") (pinfunction "S_1") (pintype "passive"))
      (node (ref "U$7") (pin "2") (pinfunction "S_2") (pintype "passive"))
      (node (ref "U$7") (pin "3") (pinfunction "S_3") (pintype "passive"))
      (node (ref "U1") (pin "4") (pinfunction "GND_4") (pintype "passive"))
      (node (ref "U1") (pin "5") (pinfunction "PGND_5") (pintype "passive"))
      (node (ref "U2") (pin "2") (pinfunction "GND_2") (pintype "passive"))
      (node (ref "U3") (pin "12") (pinfunction "GND_12") (pintype "passive"))
      (node (ref "U3") (pin "9") (pinfunction "*EN_9") (pintype "passive"))
    )
    (net (code "29") (name "MCLR") (class "Default")
      (node (ref "JP3") (pin "1") (pinfunction "1_1") (pintype "passive"))
      (node (ref "R5") (pin "1") (pinfunction "1_1") (pintype "passive"))
      (node (ref "U$1") (pin "7") (pinfunction "*MCLR_7") (pintype "passive"))
    )
    (net (code "30") (name "Net-(C7-Pad1)") (class "Default")
      (node (ref "C7") (pin "1") (pinfunction "1_1") (pintype "passive"))
      (node (ref "R5") (pin "2") (pinfunction "2_2") (pintype "passive"))
      (node (ref "R6") (pin "2") (pinfunction "2_2") (pintype "passive"))
    )
    (net (code "31") (name "Net-(C15-Pad2)") (class "Default")
      (node (ref "C15") (pin "2") (pinfunction "2_2") (pintype "passive"))
      (node (ref "R9") (pin "2") (pinfunction "2_2") (pintype "passive"))
    )
    (net (code "32") (name "Net-(C28-Pad1)") (class "Default")
      (node (ref "C28") (pin "1") (pinfunction "1_1") (pintype "passive"))
      (node (ref "R20") (pin "1") (pinfunction "1_1") (pintype "passive"))
    )
    (net (code "33") (name "Net-(L1-1)") (class "Default")
      (node (ref "C6") (pin "2") (pinfunction "2_2") (pintype "passive"))
      (node (ref "D1") (pin "C") (pinfunction "C_C") (pintype "passive"))
      (node (ref "L1") (pin "P$1") (pinfunction "1_P$1") (pintype "passive"))
      (node (ref "U$2") (pin "51") (pinfunction "PH_51") (pintype "passive"))
    )
    (net (code "34") (name "Net-(LED1-A)") (class "Default")
      (node (ref "LED1") (pin "1") (pinfunction "A_1") (pintype "passive"))
      (node (ref "RN1") (pin "P$5") (pinfunction "5_P$5") (pintype "passive"))
    )
    (net (code "35") (name "Net-(LED2-A)") (class "Default")
      (node (ref "LED2") (pin "1") (pinfunction "A_1") (pintype "passive"))
      (node (ref "RN1") (pin "P$6") (pinfunction "6_P$6") (pintype "passive"))
    )
    (net (code "36") (name "Net-(LED3-A)") (class "Default")
      (node (ref "LED3") (pin "1") (pinfunction "A_1") (pintype "passive"))
      (node (ref "RN1") (pin "P$7") (pinfunction "7_P$7") (pintype "passive"))
    )
    (net (code "37") (name "Net-(LED4-A)") (class "Default")
      (node (ref "LED4") (pin "1") (pinfunction "A_1") (pintype "passive"))
      (node (ref "RN1") (pin "P$8") (pinfunction "8_P$8") (pintype "passive"))
    )
    (net (code "38") (name "Net-(R17-Pad1)") (class "Default")
      (node (ref "R17") (pin "1") (pinfunction "1_1") (pintype "passive"))
      (node (ref "SJ8") (pin "1") (pinfunction "1_1") (pintype "passive"))
    )
    (net (code "39") (name "Net-(RN1-1)") (class "Default")
      (node (ref "RN1") (pin "P$1") (pinfunction "1_P$1") (pintype "passive"))
      (node (ref "U$1") (pin "48") (pinfunction "TCK/CVREF1O/ASCL1/RP40/T4CK/RB8_48") (pintype "passive"))
    )
    (net (code "40") (name "Net-(RN1-2)") (class "Default")
      (node (ref "RN1") (pin "P$2") (pinfunction "2_P$2") (pintype "passive"))
      (node (ref "U$1") (pin "47") (pinfunction "RC13_47") (pintype "passive"))
    )
    (net (code "41") (name "Net-(RN1-3)") (class "Default")
      (node (ref "RN1") (pin "P$3") (pinfunction "3_P$3") (pintype "passive"))
      (node (ref "U$1") (pin "46") (pinfunction "RP39/INT0/RB7_46") (pintype "passive"))
    )
    (net (code "42") (name "Net-(RN1-4)") (class "Default")
      (node (ref "RN1") (pin "P$4") (pinfunction "4_P$4") (pintype "passive"))
      (node (ref "U$1") (pin "45") (pinfunction "RPI58/RC10_45") (pintype "passive"))
    )
    (net (code "43") (name "Net-(U$1-AN6{slash}OA3OUT{slash}C4IN1+{slash}OCFB{slash}RC0)") (class "Default")
      (node (ref "JP2") (pin "3") (pinfunction "3_3") (pintype "passive"))
      (node (ref "U$1") (pin "21") (pinfunction "AN6/OA3OUT/C4IN1+/OCFB/RC0_21") (pintype "passive"))
    )
    (net (code "44") (name "Net-(U$1-AN7{slash}C3IN1-{slash}C4IN1-{slash}RC1)") (class "Default")
      (node (ref "JP2") (pin "4") (pinfunction "4_4") (pintype "passive"))
      (node (ref "U$1") (pin "22") (pinfunction "AN7/C3IN1-/C4IN1-/RC1_22") (pintype "passive"))
    )
    (net (code "45") (name "Net-(U$1-AN8{slash}C3IN1+{slash}*U1RTS{slash}BCLK1{slash}FLT3{slash}RC2)") (class "Default")
      (node (ref "JP2") (pin "5") (pinfunction "5_5") (pintype "passive"))
      (node (ref "U$1") (pin "23") (pinfunction "AN8/C3IN1+/*U1RTS/BCLK1/FLT3/RC2_23") (pintype "passive"))
    )
    (net (code "46") (name "Net-(U$1-AN12{slash}C2IN2-{slash}*U2RTS{slash}BCLK2{slash}RE12)") (class "Default")
      (node (ref "JP1") (pin "1") (pinfunction "1_1") (pintype "passive"))
      (node (ref "U$1") (pin "27") (pinfunction "AN12/C2IN2-/*U2RTS/BCLK2/RE12_27") (pintype "passive"))
    )
    (net (code "47") (name "Net-(U$1-AN13{slash}C3IN2-{slash}*U2CTS{slash}RE13)") (class "Default")
      (node (ref "JP1") (pin "2") (pinfunction "2_2") (pintype "passive"))
      (node (ref "U$1") (pin "28") (pinfunction "AN13/C3IN2-/*U2CTS/RE13_28") (pintype "passive"))
    )
    (net (code "48") (name "Net-(U$1-AN14{slash}RPI94{slash}RE14)") (class "Default")
      (node (ref "JP1") (pin "3") (pinfunction "3_3") (pintype "passive"))
      (node (ref "U$1") (pin "29") (pinfunction "AN14/RPI94/RE14_29") (pintype "passive"))
    )
    (net (code "49") (name "Net-(U$1-AN15{slash}RPI95{slash}RE15)") (class "Default")
      (node (ref "JP1") (pin "4") (pinfunction "4_4") (pintype "passive"))
      (node (ref "U$1") (pin "30") (pinfunction "AN15/RPI95/RE15_30") (pintype "passive"))
    )
    (net (code "50") (name "Net-(U$1-AVDD)") (class "Default")
      (node (ref "C24") (pin "1") (pinfunction "1_1") (pintype "passive"))
      (node (ref "U$1") (pin "19") (pinfunction "AVDD_19") (pintype "passive"))
    )
    (net (code "51") (name "Net-(U$1-AVSS)") (class "Default")
      (node (ref "C24") (pin "2") (pinfunction "2_2") (pintype "passive"))
      (node (ref "U$1") (pin "20") (pinfunction "AVSS_20") (pintype "passive"))
    )
    (net (code "52") (name "Net-(U$1-FLT32{slash}SCL2{slash}RP36{slash}RB4)") (class "Default")
      (node (ref "JP1") (pin "6") (pinfunction "6_6") (pintype "passive"))
      (node (ref "U$1") (pin "32") (pinfunction "FLT32/SCL2/RP36/RB4_32") (pintype "passive"))
    )
    (net (code "53") (name "Net-(U$1-PGEC3{slash}VREF+{slash}AN3{slash}OA1OUT{slash}RPI33{slash}CTED1{slash}RB1)") (class "Default")
      (node (ref "JP2") (pin "2") (pinfunction "2_2") (pintype "passive"))
      (node (ref "U$1") (pin "16") (pinfunction "PGEC3/VREF+/AN3/OA1OUT/RPI33/CTED1/RB1_16") (pintype "passive"))
    )
    (net (code "54") (name "Net-(U$1-PGED3{slash}VREF-{slash}AN2{slash}C2IN1-{slash}*SS1{slash}RPI32{slash}CTED2{slash}RB0)") (class "Default")
      (node (ref "R18") (pin "2") (pinfunction "2_2") (pintype "passive"))
      (node (ref "R19") (pin "1") (pinfunction "1_1") (pintype "passive"))
      (node (ref "U$1") (pin "15") (pinfunction "PGED3/VREF-/AN2/C2IN1-/*SS1/RPI32/CTED2/RB0_15") (pintype "passive"))
    )
    (net (code "55") (name "Net-(U$1-RP118{slash}RG6)") (class "Default")
      (node (ref "SJ4") (pin "2") (pinfunction "2_2") (pintype "passive"))
      (node (ref "U$1") (pin "4") (pinfunction "RP118/RG6_4") (pintype "passive"))
    )
    (net (code "56") (name "Net-(U$1-RP120{slash}RG8)") (class "Default")
      (node (ref "SJ6") (pin "2") (pinfunction "2_2") (pintype "passive"))
      (node (ref "U$1") (pin "6") (pinfunction "RP120/RG8_6") (pintype "passive"))
    )
    (net (code "57") (name "Net-(U$1-RPI47{slash}PWM1L{slash}T5CK{slash}RB15)") (class "Default")
      (node (ref "SJ1") (pin "2") (pinfunction "2_2") (pintype "passive"))
      (node (ref "U$1") (pin "3") (pinfunction "RPI47/PWM1L/T5CK/RB15_3") (pintype "passive"))
    )
    (net (code "58") (name "Net-(U$1-RPI119{slash}RG7)") (class "Default")
      (node (ref "SJ5") (pin "2") (pinfunction "2_2") (pintype "passive"))
      (node (ref "U$1") (pin "5") (pinfunction "RPI119/RG7_5") (pintype "passive"))
    )
    (net (code "59") (name "Net-(U$1-RPI121{slash}RG9)") (class "Default")
      (node (ref "SJ7") (pin "2") (pinfunction "2_2") (pintype "passive"))
      (node (ref "U$1") (pin "8") (pinfunction "RPI121/RG9_8") (pintype "passive"))
    )
    (net (code "60") (name "Net-(U$1-SDA2{slash}RPI24{slash}RA8)") (class "Default")
      (node (ref "JP1") (pin "5") (pinfunction "5_5") (pintype "passive"))
      (node (ref "U$1") (pin "31") (pinfunction "SDA2/RPI24/RA8_31") (pintype "passive"))
    )
    (net (code "61") (name "Net-(U$1-VCAP)") (class "Default")
      (node (ref "C20") (pin "1") (pinfunction "1_1") (pintype "passive"))
      (node (ref "U$1") (pin "56") (pinfunction "VCAP_56") (pintype "passive"))
    )
    (net (code "62") (name "Net-(U$1-VDD)") (class "Default")
      (node (ref "C21") (pin "1") (pinfunction "1_1") (pintype "passive"))
      (node (ref "U$1") (pin "57") (pinfunction "VDD_57") (pintype "passive"))
    )
    (net (code "63") (name "Net-(U$1-VDD_2)") (class "Default")
      (node (ref "C25") (pin "1") (pinfunction "1_1") (pintype "passive"))
      (node (ref "U$1") (pin "10") (pinfunction "VDD_2_10") (pintype "passive"))
    )
    (net (code "64") (name "Net-(U$1-VDD_3)") (class "Default")
      (node (ref "C23") (pin "2") (pinfunction "2_2") (pintype "passive"))
      (node (ref "U$1") (pin "26") (pinfunction "VDD_3_26") (pintype "passive"))
    )
    (net (code "65") (name "Net-(U$1-VDD_4)") (class "Default")
      (node (ref "C22") (pin "2") (pinfunction "2_2") (pintype "passive"))
      (node (ref "U$1") (pin "38") (pinfunction "VDD_4_38") (pintype "passive"))
    )
    (net (code "66") (name "Net-(U$1-VSS_2)") (class "Default")
      (node (ref "C25") (pin "2") (pinfunction "2_2") (pintype "passive"))
      (node (ref "U$1") (pin "9") (pinfunction "VSS_2_9") (pintype "passive"))
    )
    (net (code "67") (name "Net-(U$1-VSS_3)") (class "Default")
      (node (ref "C23") (pin "1") (pinfunction "1_1") (pintype "passive"))
      (node (ref "U$1") (pin "25") (pinfunction "VSS_3_25") (pintype "passive"))
    )
    (net (code "68") (name "Net-(U$2-AVDD)") (class "Default")
      (node (ref "C19") (pin "2") (pinfunction "2_2") (pintype "passive"))
      (node (ref "U$2") (pin "27") (pinfunction "AVDD_27") (pintype "passive"))
    )
    (net (code "69") (name "Net-(U$2-BIAS)") (class "Default")
      (node (ref "R3") (pin "1") (pinfunction "1_1") (pintype "passive"))
      (node (ref "U$2") (pin "49") (pinfunction "BIAS_49") (pintype "passive"))
    )
    (net (code "70") (name "Net-(U$2-BST_A)") (class "Default")
      (node (ref "C9") (pin "1") (pinfunction "1_1") (pintype "passive"))
      (node (ref "U$2") (pin "48") (pinfunction "BST_A_48") (pintype "passive"))
    )
    (net (code "71") (name "Net-(U$2-BST_B)") (class "Default")
      (node (ref "C10") (pin "1") (pinfunction "1_1") (pintype "passive"))
      (node (ref "U$2") (pin "43") (pinfunction "BST_B_43") (pintype "passive"))
    )
    (net (code "72") (name "Net-(U$2-BST_BK)") (class "Default")
      (node (ref "C6") (pin "1") (pinfunction "1_1") (pintype "passive"))
      (node (ref "U$2") (pin "52") (pinfunction "BST_BK_52") (pintype "passive"))
    )
    (net (code "73") (name "Net-(U$2-BST_C)") (class "Default")
      (node (ref "C11") (pin "1") (pinfunction "1_1") (pintype "passive"))
      (node (ref "U$2") (pin "38") (pinfunction "BST_C_38") (pintype "passive"))
    )
    (net (code "74") (name "Net-(U$2-COMP)") (class "Default")
      (node (ref "C14") (pin "2") (pinfunction "2_2") (pintype "passive"))
      (node (ref "R9") (pin "1") (pinfunction "1_1") (pintype "passive"))
      (node (ref "U$2") (pin "2") (pinfunction "COMP_2") (pintype "passive"))
    )
    (net (code "75") (name "Net-(U$2-CP1)") (class "Default")
      (node (ref "C17") (pin "1") (pinfunction "1_1") (pintype "passive"))
      (node (ref "U$2") (pin "14") (pinfunction "CP1_14") (pintype "passive"))
    )
    (net (code "76") (name "Net-(U$2-CP2)") (class "Default")
      (node (ref "C17") (pin "2") (pinfunction "2_2") (pintype "passive"))
      (node (ref "U$2") (pin "15") (pinfunction "CP2_15") (pintype "passive"))
    )
    (net (code "77") (name "Net-(U$2-DVDD)") (class "Default")
      (node (ref "C18") (pin "2") (pinfunction "2_2") (pintype "passive"))
      (node (ref "R15") (pin "1") (pinfunction "1_1") (pintype "passive"))
      (node (ref "U$2") (pin "23") (pinfunction "DVDD_23") (pintype "passive"))
    )
    (net (code "78") (name "Net-(U$2-GVDD)") (class "Default")
      (node (ref "C16") (pin "1") (pinfunction "1_1") (pintype "passive"))
      (node (ref "U$2") (pin "13") (pinfunction "GVDD_13") (pintype "passive"))
    )
    (net (code "79") (name "Net-(U$2-OC_ADJ)") (class "Default")
      (node (ref "R15") (pin "2") (pinfunction "2_2") (pintype "passive"))
      (node (ref "R16") (pin "1") (pinfunction "1_1") (pintype "passive"))
      (node (ref "U$2") (pin "11") (pinfunction "OC_ADJ_11") (pintype "passive"))
    )
    (net (code "80") (name "Net-(U$2-RT_CLK)") (class "Default")
      (node (ref "R8") (pin "1") (pinfunction "1_1") (pintype "passive"))
      (node (ref "U$2") (pin "1") (pinfunction "RT_CLK_1") (pintype "passive"))
    )
    (net (code "81") (name "Net-(U$2-SS_TR)") (class "Default")
      (node (ref "C5") (pin "1") (pinfunction "1_1") (pintype "passive"))
      (node (ref "U$2") (pin "56") (pinfunction "SS_TR_56") (pintype "passive"))
    )
    (net (code "82") (name "Net-(U$2-VSENSE)") (class "Default")
      (node (ref "R10") (pin "1") (pinfunction "1_1") (pintype "passive"))
      (node (ref "R11") (pin "2") (pinfunction "2_2") (pintype "passive"))
      (node (ref "U$2") (pin "3") (pinfunction "VSENSE_3") (pintype "passive"))
    )
    (net (code "83") (name "Net-(U1-CPUMP+)") (class "Default")
      (node (ref "C29") (pin "1") (pinfunction "1_1") (pintype "passive"))
      (node (ref "U1") (pin "7") (pinfunction "CPUMP+_7") (pintype "passive"))
    )
    (net (code "84") (name "Net-(U1-CPUMP-)") (class "Default")
      (node (ref "C29") (pin "2") (pinfunction "2_2") (pintype "passive"))
      (node (ref "U1") (pin "6") (pinfunction "CPUMP-_6") (pintype "passive"))
    )
    (net (code "85") (name "OCTW") (class "Default")
      (node (ref "R13") (pin "1") (pinfunction "1_1") (pintype "passive"))
      (node (ref "U$1") (pin "53") (pinfunction "RD5_53") (pintype "passive"))
      (node (ref "U$2") (pin "5") (pinfunction "*OCTW_5") (pintype "passive"))
    )
    (net (code "86") (name "OUT_U") (class "Default")
      (node (ref "C9") (pin "2") (pinfunction "2_2") (pintype "passive"))
      (node (ref "JP7") (pin "3") (pinfunction "3_3") (pintype "passive"))
      (node (ref "U$2") (pin "46") (pinfunction "SH_A_46") (pintype "passive"))
      (node (ref "U$3") (pin "1") (pinfunction "S_1") (pintype "passive"))
      (node (ref "U$3") (pin "2") (pinfunction "S_2") (pintype "passive"))
      (node (ref "U$3") (pin "3") (pinfunction "S_3") (pintype "passive"))
      (node (ref "U$6") (pin "5") (pinfunction "D_5") (pintype "passive"))
      (node (ref "U$6") (pin "P$1") (pinfunction "D_P$1") (pintype "passive"))
      (node (ref "U$6") (pin "P$2") (pinfunction "D_P$2") (pintype "passive"))
      (node (ref "U$6") (pin "P$3") (pinfunction "D_P$3") (pintype "passive"))
      (node (ref "U$6") (pin "P$4") (pinfunction "D_P$4") (pintype "passive"))
      (node (ref "U$6") (pin "P$5") (pinfunction "D_P$5") (pintype "passive"))
      (node (ref "U$6") (pin "P$6") (pinfunction "D_P$6") (pintype "passive"))
      (node (ref "U$6") (pin "P$7") (pinfunction "D_P$7") (pintype "passive"))
      (node (ref "U$6") (pin "P$8") (pinfunction "D_P$8") (pintype "passive"))
      (node (ref "U$6") (pin "P$9") (pinfunction "D_P$9") (pintype "passive"))
    )
    (net (code "87") (name "OUT_V") (class "Default")
      (node (ref "C10") (pin "2") (pinfunction "2_2") (pintype "passive"))
      (node (ref "JP7") (pin "2") (pinfunction "2_2") (pintype "passive"))
      (node (ref "U$2") (pin "41") (pinfunction "SH_B_41") (pintype "passive"))
      (node (ref "U$4") (pin "1") (pinfunction "S_1") (pintype "passive"))
      (node (ref "U$4") (pin "2") (pinfunction "S_2") (pintype "passive"))
      (node (ref "U$4") (pin "3") (pinfunction "S_3") (pintype "passive"))
      (node (ref "U$7") (pin "5") (pinfunction "D_5") (pintype "passive"))
      (node (ref "U$7") (pin "P$1") (pinfunction "D_P$1") (pintype "passive"))
      (node (ref "U$7") (pin "P$2") (pinfunction "D_P$2") (pintype "passive"))
      (node (ref "U$7") (pin "P$3") (pinfunction "D_P$3") (pintype "passive"))
      (node (ref "U$7") (pin "P$4") (pinfunction "D_P$4") (pintype "passive"))
      (node (ref "U$7") (pin "P$5") (pinfunction "D_P$5") (pintype "passive"))
      (node (ref "U$7") (pin "P$6") (pinfunction "D_P$6") (pintype "passive"))
      (node (ref "U$7") (pin "P$7") (pinfunction "D_P$7") (pintype "passive"))
      (node (ref "U$7") (pin "P$8") (pinfunction "D_P$8") (pintype "passive"))
      (node (ref "U$7") (pin "P$9") (pinfunction "D_P$9") (pintype "passive"))
    )
    (net (code "88") (name "OUT_W") (class "Default")
      (node (ref "C11") (pin "2") (pinfunction "2_2") (pintype "passive"))
      (node (ref "JP7") (pin "1") (pinfunction "1_1") (pintype "passive"))
      (node (ref "U$2") (pin "36") (pinfunction "SH_C_36") (pintype "passive"))
      (node (ref "U$5") (pin "1") (pinfunction "S_1") (pintype "passive"))
      (node (ref "U$5") (pin "2") (pinfunction "S_2") (pintype "passive"))
      (node (ref "U$5") (pin "3") (pinfunction "S_3") (pintype "passive"))
      (node (ref "U$8") (pin "5") (pinfunction "D_5") (pintype "passive"))
      (node (ref "U$8") (pin "P$1") (pinfunction "D_P$1") (pintype "passive"))
      (node (ref "U$8") (pin "P$2") (pinfunction "D_P$2") (pintype "passive"))
      (node (ref "U$8") (pin "P$3") (pinfunction "D_P$3") (pintype "passive"))
      (node (ref "U$8") (pin "P$4") (pinfunction "D_P$4") (pintype "passive"))
      (node (ref "U$8") (pin "P$5") (pinfunction "D_P$5") (pintype "passive"))
      (node (ref "U$8") (pin "P$6") (pinfunction "D_P$6") (pintype "passive"))
      (node (ref "U$8") (pin "P$7") (pinfunction "D_P$7") (pintype "passive"))
      (node (ref "U$8") (pin "P$8") (pinfunction "D_P$8") (pintype "passive"))
      (node (ref "U$8") (pin "P$9") (pinfunction "D_P$9") (pintype "passive"))
    )
    (net (code "89") (name "PGC") (class "Default")
      (node (ref "JP3") (pin "5") (pinfunction "5_5") (pintype "passive"))
      (node (ref "U$1") (pin "44") (pinfunction "PGEC2/ASCL2/RP38/RB6_44") (pintype "passive"))
    )
    (net (code "90") (name "PGD") (class "Default")
      (node (ref "JP3") (pin "4") (pinfunction "4_4") (pintype "passive"))
      (node (ref "U$1") (pin "43") (pinfunction "PGED2/ASDA2/RP37/RB5_43") (pintype "passive"))
    )
    (net (code "91") (name "PVDD") (class "Default")
      (node (ref "C1") (pin "1") (pinfunction "1_1") (pintype "passive"))
      (node (ref "C2") (pin "1") (pinfunction "1_1") (pintype "passive"))
      (node (ref "C27") (pin "1") (pinfunction "+_1") (pintype "passive"))
      (node (ref "C3") (pin "1") (pinfunction "1_1") (pintype "passive"))
      (node (ref "C4") (pin "1") (pinfunction "1_1") (pintype "passive"))
      (node (ref "F1") (pin "A") (pinfunction "1_A") (pintype "passive"))
      (node (ref "J2") (pin "2") (pinfunction "1_2") (pintype "passive"))
      (node (ref "JP2") (pin "1") (pinfunction "1_1") (pintype "passive"))
      (node (ref "R18") (pin "1") (pinfunction "1_1") (pintype "passive"))
      (node (ref "R20") (pin "2") (pinfunction "2_2") (pintype "passive"))
      (node (ref "U$2") (pin "29") (pinfunction "PVDD1_29") (pintype "passive"))
      (node (ref "U$2") (pin "53") (pinfunction "PVDD2_53") (pintype "passive"))
      (node (ref "U$2") (pin "54") (pinfunction "PVDD2_2_54") (pintype "passive"))
      (node (ref "U$3") (pin "5") (pinfunction "D_5") (pintype "passive"))
      (node (ref "U$3") (pin "P$1") (pinfunction "D_P$1") (pintype "passive"))
      (node (ref "U$3") (pin "P$2") (pinfunction "D_P$2") (pintype "passive"))
      (node (ref "U$3") (pin "P$3") (pinfunction "D_P$3") (pintype "passive"))
      (node (ref "U$3") (pin "P$4") (pinfunction "D_P$4") (pintype "passive"))
      (node (ref "U$3") (pin "P$5") (pinfunction "D_P$5") (pintype "passive"))
      (node (ref "U$3") (pin "P$6") (pinfunction "D_P$6") (pintype "passive"))
      (node (ref "U$3") (pin "P$7") (pinfunction "D_P$7") (pintype "passive"))
      (node (ref "U$3") (pin "P$8") (pinfunction "D_P$8") (pintype "passive"))
      (node (ref "U$3") (pin "P$9") (pinfunction "D_P$9") (pintype "passive"))
      (node (ref "U$4") (pin "5") (pinfunction "D_5") (pintype "passive"))
      (node (ref "U$4") (pin "P$1") (pinfunction "D_P$1") (pintype "passive"))
      (node (ref "U$4") (pin "P$2") (pinfunction "D_P$2") (pintype "passive"))
      (node (ref "U$4") (pin "P$3") (pinfunction "D_P$3") (pintype "passive"))
      (node (ref "U$4") (pin "P$4") (pinfunction "D_P$4") (pintype "passive"))
      (node (ref "U$4") (pin "P$5") (pinfunction "D_P$5") (pintype "passive"))
      (node (ref "U$4") (pin "P$6") (pinfunction "D_P$6") (pintype "passive"))
      (node (ref "U$4") (pin "P$7") (pinfunction "D_P$7") (pintype "passive"))
      (node (ref "U$4") (pin "P$8") (pinfunction "D_P$8") (pintype "passive"))
      (node (ref "U$4") (pin "P$9") (pinfunction "D_P$9") (pintype "passive"))
      (node (ref "U$5") (pin "5") (pinfunction "D_5") (pintype "passive"))
      (node (ref "U$5") (pin "P$1") (pinfunction "D_P$1") (pintype "passive"))
      (node (ref "U$5") (pin "P$2") (pinfunction "D_P$2") (pintype "passive"))
      (node (ref "U$5") (pin "P$3") (pinfunction "D_P$3") (pintype "passive"))
      (node (ref "U$5") (pin "P$4") (pinfunction "D_P$4") (pintype "passive"))
      (node (ref "U$5") (pin "P$5") (pinfunction "D_P$5") (pintype "passive"))
      (node (ref "U$5") (pin "P$6") (pinfunction "D_P$6") (pintype "passive"))
      (node (ref "U$5") (pin "P$7") (pinfunction "D_P$7") (pintype "passive"))
      (node (ref "U$5") (pin "P$8") (pinfunction "D_P$8") (pintype "passive"))
      (node (ref "U$5") (pin "P$9") (pinfunction "D_P$9") (pintype "passive"))
    )
    (net (code "92") (name "PWM1") (class "Default")
      (node (ref "U$1") (pin "2") (pinfunction "RPI46/PWM1H/T3CK/RB14_2") (pintype "passive"))
      (node (ref "U$2") (pin "17") (pinfunction "INH_A_17") (pintype "passive"))
    )
    (net (code "93") (name "PWM3") (class "Default")
      (node (ref "U$1") (pin "62") (pinfunction "RPI44/PWM2H/RB12_62") (pintype "passive"))
      (node (ref "U$2") (pin "19") (pinfunction "INH_B_19") (pintype "passive"))
    )
    (net (code "94") (name "PWM5") (class "Default")
      (node (ref "U$1") (pin "60") (pinfunction "RP42/PWM3H/RB10_60") (pintype "passive"))
      (node (ref "U$2") (pin "21") (pinfunction "INH_C_21") (pintype "passive"))
    )
    (net (code "95") (name "PWRGD") (class "Default")
      (node (ref "R12") (pin "1") (pinfunction "1_1") (pintype "passive"))
      (node (ref "U$1") (pin "54") (pinfunction "RD6_54") (pintype "passive"))
      (node (ref "U$2") (pin "4") (pinfunction "PWRGD_4") (pintype "passive"))
    )
    (net (code "96") (name "RA11") (class "Default")
      (node (ref "JP5") (pin "3") (pinfunction "3_3") (pintype "passive"))
      (node (ref "U$1") (pin "12") (pinfunction "AN9/RPI27/RA11_12") (pintype "passive"))
    )
    (net (code "97") (name "RA12") (class "Default")
      (node (ref "JP5") (pin "2") (pinfunction "2_2") (pintype "passive"))
      (node (ref "U$1") (pin "11") (pinfunction "AN10/RPI28/RA12_11") (pintype "passive"))
    )
    (net (code "98") (name "SN1") (class "Default")
      (node (ref "C12") (pin "1") (pinfunction "1_1") (pintype "passive"))
      (node (ref "R7") (pin "2") (pinfunction "2_2") (pintype "passive"))
      (node (ref "U$2") (pin "33") (pinfunction "SN1_33") (pintype "passive"))
      (node (ref "U$2") (pin "44") (pinfunction "SL_A_44") (pintype "passive"))
      (node (ref "U$6") (pin "1") (pinfunction "S_1") (pintype "passive"))
      (node (ref "U$6") (pin "2") (pinfunction "S_2") (pintype "passive"))
      (node (ref "U$6") (pin "3") (pinfunction "S_3") (pintype "passive"))
    )
    (net (code "99") (name "SN2") (class "Default")
      (node (ref "C13") (pin "1") (pinfunction "1_1") (pintype "passive"))
      (node (ref "R4") (pin "2") (pinfunction "2_2") (pintype "passive"))
      (node (ref "U$2") (pin "31") (pinfunction "SN2_31") (pintype "passive"))
      (node (ref "U$2") (pin "34") (pinfunction "SL_C_34") (pintype "passive"))
      (node (ref "U$8") (pin "1") (pinfunction "S_1") (pintype "passive"))
      (node (ref "U$8") (pin "2") (pinfunction "S_2") (pintype "passive"))
      (node (ref "U$8") (pin "3") (pinfunction "S_3") (pintype "passive"))
    )
    (net (code "100") (name "VCC3V3") (class "Default")
      (node (ref "C26") (pin "1") (pinfunction "1_1") (pintype "passive"))
      (node (ref "C31") (pin "1") (pinfunction "1_1") (pintype "passive"))
      (node (ref "C8") (pin "1") (pinfunction "1_1") (pintype "passive"))
      (node (ref "JP3") (pin "2") (pinfunction "2_2") (pintype "passive"))
      (node (ref "JP5") (pin "1") (pinfunction "1_1") (pintype "passive"))
      (node (ref "L1") (pin "P$2") (pinfunction "2_P$2") (pintype "passive"))
      (node (ref "R10") (pin "2") (pinfunction "2_2") (pintype "passive"))
      (node (ref "R12") (pin "2") (pinfunction "2_2") (pintype "passive"))
      (node (ref "R13") (pin "2") (pinfunction "2_2") (pintype "passive"))
      (node (ref "R14") (pin "2") (pinfunction "2_2") (pintype "passive"))
      (node (ref "R6") (pin "1") (pinfunction "1_1") (pintype "passive"))
      (node (ref "SJ1") (pin "1") (pinfunction "1_1") (pintype "passive"))
      (node (ref "SJ4") (pin "1") (pinfunction "1_1") (pintype "passive"))
      (node (ref "SJ5") (pin "1") (pinfunction "1_1") (pintype "passive"))
      (node (ref "SJ6") (pin "1") (pinfunction "1_1") (pintype "passive"))
      (node (ref "SJ7") (pin "1") (pinfunction "1_1") (pintype "passive"))
      (node (ref "U$2") (pin "24") (pinfunction "REF_24") (pintype "passive"))
      (node (ref "U$2") (pin "8") (pinfunction "M_PWM_8") (pintype "passive"))
      (node (ref "U1") (pin "2") (pinfunction "ENABLE_2") (pintype "passive"))
      (node (ref "U1") (pin "3") (pinfunction "VIN_3") (pintype "passive"))
      (node (ref "U2") (pin "3") (pinfunction "VCC_3") (pintype "passive"))
      (node (ref "U3") (pin "13") (pinfunction "VCC_13") (pintype "passive"))
      (node (ref "U3") (pin "16") (pinfunction "EN_16") (pintype "passive"))
    )
    (net (code "101") (name "VCC5V") (class "Default")
      (node (ref "C30") (pin "2") (pinfunction "2_2") (pintype "passive"))
      (node (ref "JP5") (pin "6") (pinfunction "6_6") (pintype "passive"))
      (node (ref "U1") (pin "8") (pinfunction "VOUT_8") (pintype "passive"))
    )
    (net (code "102") (name "V_IN") (class "Default")
      (node (ref "F1") (pin "C") (pinfunction "2_C") (pintype "passive"))
      (node (ref "J1") (pin "2") (pinfunction "1_2") (pintype "passive"))
    )
    (net (code "103") (name "unconnected-(JP3-Pad6)") (class "Default")
      (node (ref "JP3") (pin "6") (pinfunction "6_6") (pintype "passive"))
    )
    (net (code "104") (name "unconnected-(U$1-AN11{slash}C1IN2-{slash}*U1CTS{slash}FLT4{slash}RC11-Pad24)") (class "Default")
      (node (ref "U$1") (pin "24") (pinfunction "AN11/C1IN2-/*U1CTS/FLT4/RC11_24") (pintype "passive"))
    )
    (net (code "105") (name "unconnected-(U$1-CVREF2O{slash}SDO1{slash}RP20{slash}T1CK{slash}RA4-Pad33)") (class "Default")
      (node (ref "U$1") (pin "33") (pinfunction "CVREF2O/SDO1/RP20/T1CK/RA4_33") (pintype "passive"))
    )
    (net (code "106") (name "unconnected-(U$1-OSC1{slash}CLKI{slash}RC12-Pad39)") (class "Default")
      (node (ref "U$1") (pin "39") (pinfunction "OSC1/CLKI/RC12_39") (pintype "passive"))
    )
    (net (code "107") (name "unconnected-(U$1-OSC2{slash}CLKO{slash}RC15-Pad40)") (class "Default")
      (node (ref "U$1") (pin "40") (pinfunction "OSC2/CLKO/RC15_40") (pintype "passive"))
    )
    (net (code "108") (name "unconnected-(U$1-RB43{slash}PWM3L{slash}RB11-Pad61)") (class "Default")
      (node (ref "U$1") (pin "61") (pinfunction "RB43/PWM3L/RB11_61") (pintype "passive"))
    )
    (net (code "109") (name "unconnected-(U$1-RD8-Pad42)") (class "Default")
      (node (ref "U$1") (pin "42") (pinfunction "RD8_42") (pintype "passive"))
    )
    (net (code "110") (name "unconnected-(U$1-RP57{slash}RC9-Pad55)") (class "Default")
      (node (ref "U$1") (pin "55") (pinfunction "RP57/RC9_55") (pintype "passive"))
    )
    (net (code "111") (name "unconnected-(U$1-RPI45{slash}PWM2L{slash}CTPLS{slash}RB13-Pad63)") (class "Default")
      (node (ref "U$1") (pin "63") (pinfunction "RPI45/PWM2L/CTPLS/RB13_63") (pintype "passive"))
    )
    (net (code "112") (name "unconnected-(U$1-SCL1{slash}RPI53{slash}RC5-Pad37)") (class "Default")
      (node (ref "U$1") (pin "37") (pinfunction "SCL1/RPI53/RC5_37") (pintype "passive"))
    )
    (net (code "113") (name "unconnected-(U$1-TDI{slash}RA7-Pad1)") (class "Default")
      (node (ref "U$1") (pin "1") (pinfunction "TDI/RA7_1") (pintype "passive"))
    )
    (net (code "114") (name "unconnected-(U$1-TDO{slash}RA10-Pad64)") (class "Default")
      (node (ref "U$1") (pin "64") (pinfunction "TDO/RA10_64") (pintype "passive"))
    )
    (net (code "115") (name "unconnected-(U$2-EN_BUCK-Pad55)") (class "Default")
      (node (ref "U$2") (pin "55") (pinfunction "EN_BUCK_55") (pintype "passive"))
    )
    (net (code "116") (name "unconnected-(U$2-INL_A-Pad18)") (class "Default")
      (node (ref "U$2") (pin "18") (pinfunction "INL_A_18") (pintype "passive"))
    )
    (net (code "117") (name "unconnected-(U$2-INL_B-Pad20)") (class "Default")
      (node (ref "U$2") (pin "20") (pinfunction "INL_B_20") (pintype "passive"))
    )
    (net (code "118") (name "unconnected-(U$2-INL_C-Pad22)") (class "Default")
      (node (ref "U$2") (pin "22") (pinfunction "INL_C_22") (pintype "passive"))
    )
    (net (code "119") (name "unconnected-(U$2-PH_2-Pad50)") (class "Default")
      (node (ref "U$2") (pin "50") (pinfunction "PH_2_50") (pintype "passive"))
    )
    (net (code "120") (name "unconnected-(U1-NC-Pad1)") (class "Default")
      (node (ref "U1") (pin "1") (pinfunction "NC_1") (pintype "passive"))
    )
    (net (code "121") (name "unconnected-(U2-NC-Pad8)") (class "Default")
      (node (ref "U2") (pin "8") (pinfunction "NC_8") (pintype "passive"))
    )
    (net (code "122") (name "unconnected-(U2-NC_2-Pad5)") (class "Default")
      (node (ref "U2") (pin "5") (pinfunction "NC_2_5") (pintype "passive"))
    )
    (net (code "123") (name "unconnected-(U3-RIN4+-Pad7)") (class "Default")
      (node (ref "U3") (pin "7") (pinfunction "RIN4+_7") (pintype "passive"))
    )
    (net (code "124") (name "unconnected-(U3-RIN4-Pad8)") (class "Default")
      (node (ref "U3") (pin "8") (pinfunction "RIN4_8") (pintype "passive"))
    )
    (net (code "125") (name "unconnected-(U3-ROUT4-Pad10)") (class "Default")
      (node (ref "U3") (pin "10") (pinfunction "ROUT4_10") (pintype "passive"))
    )
  )
)
